# node.net
KiCad netlist of a schematic drawn in EAGLE
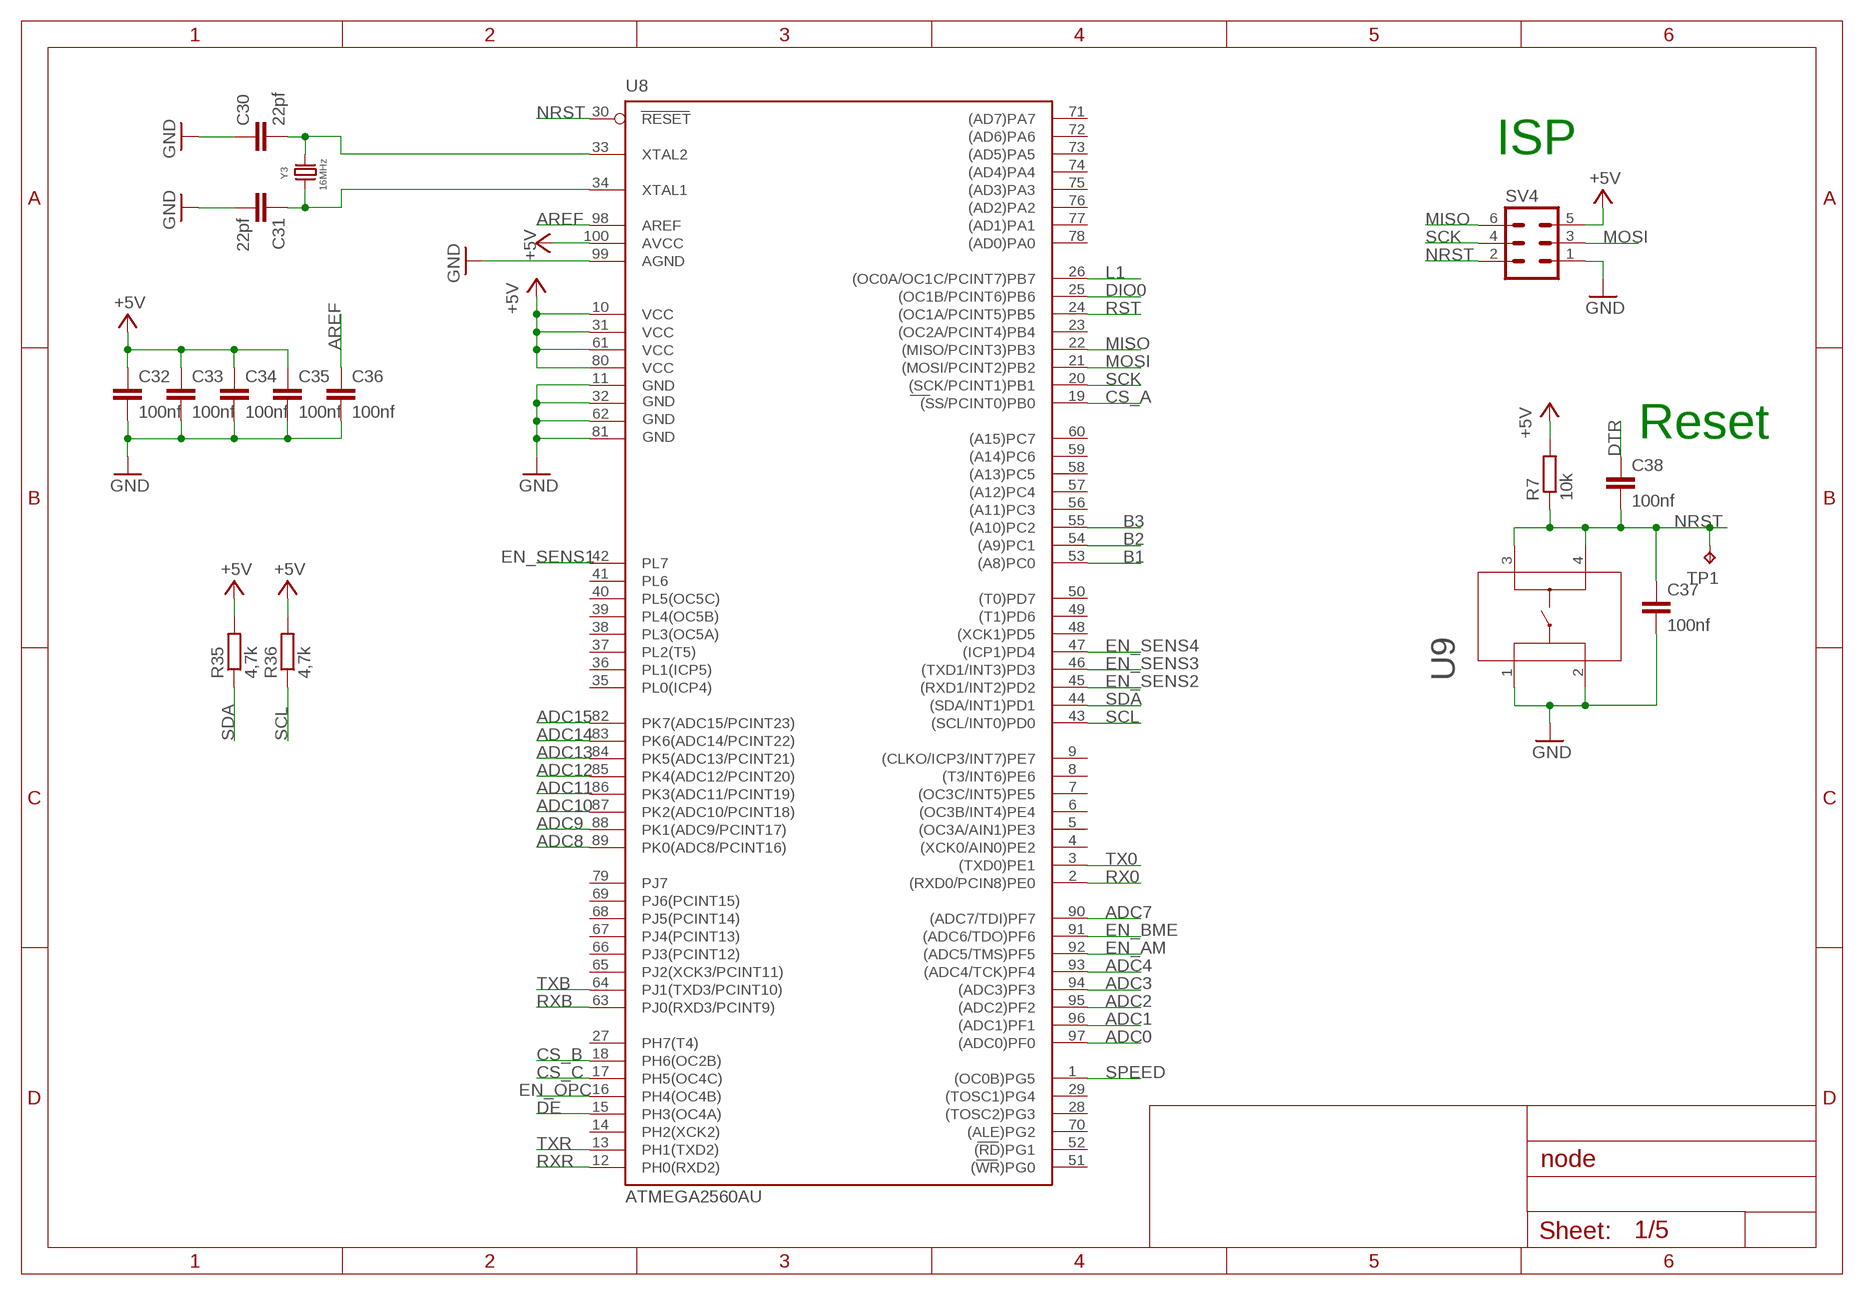
[diagram p0: schematic, sheet 1]
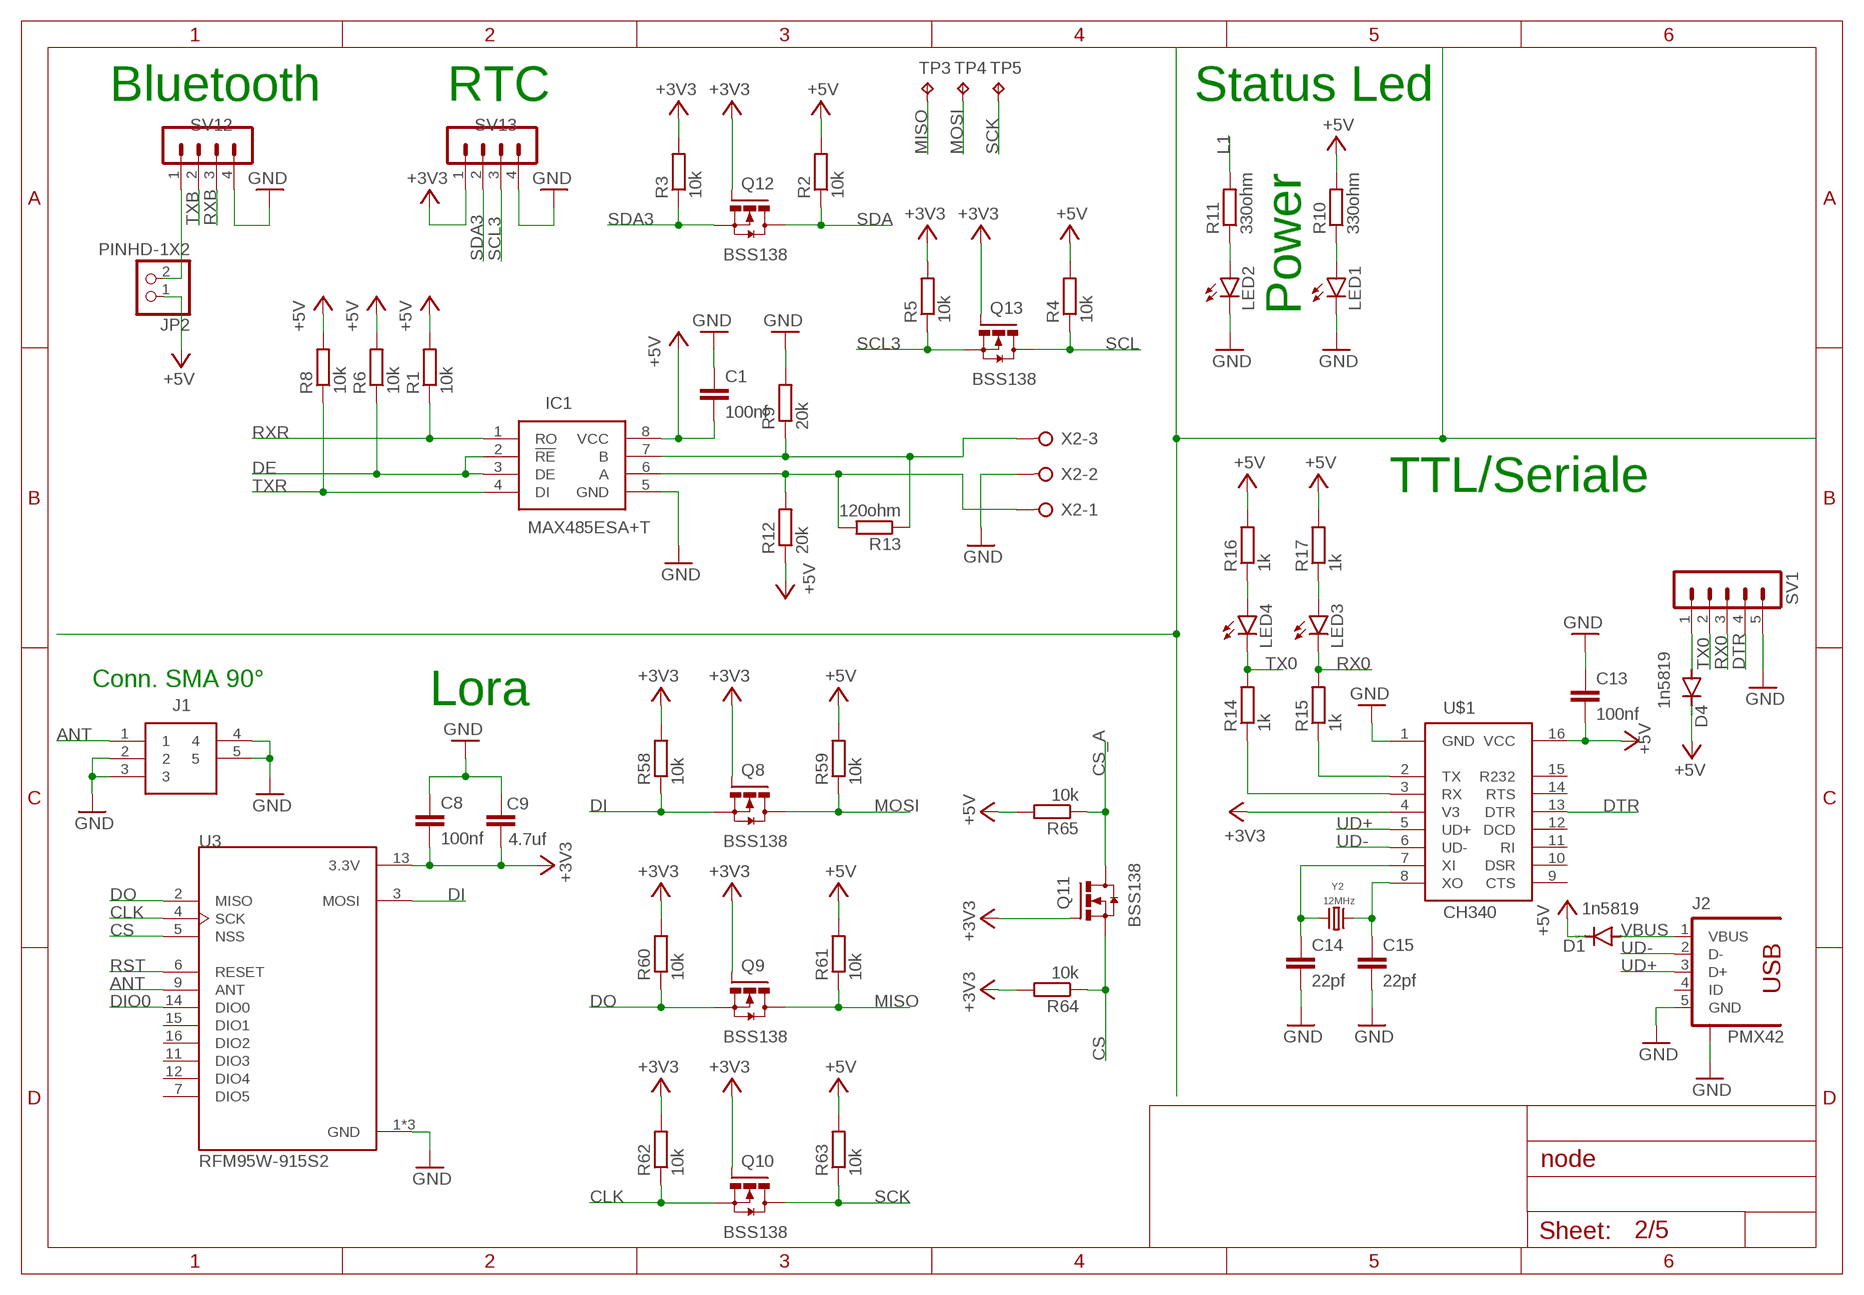
[diagram p1: schematic, sheet 2]
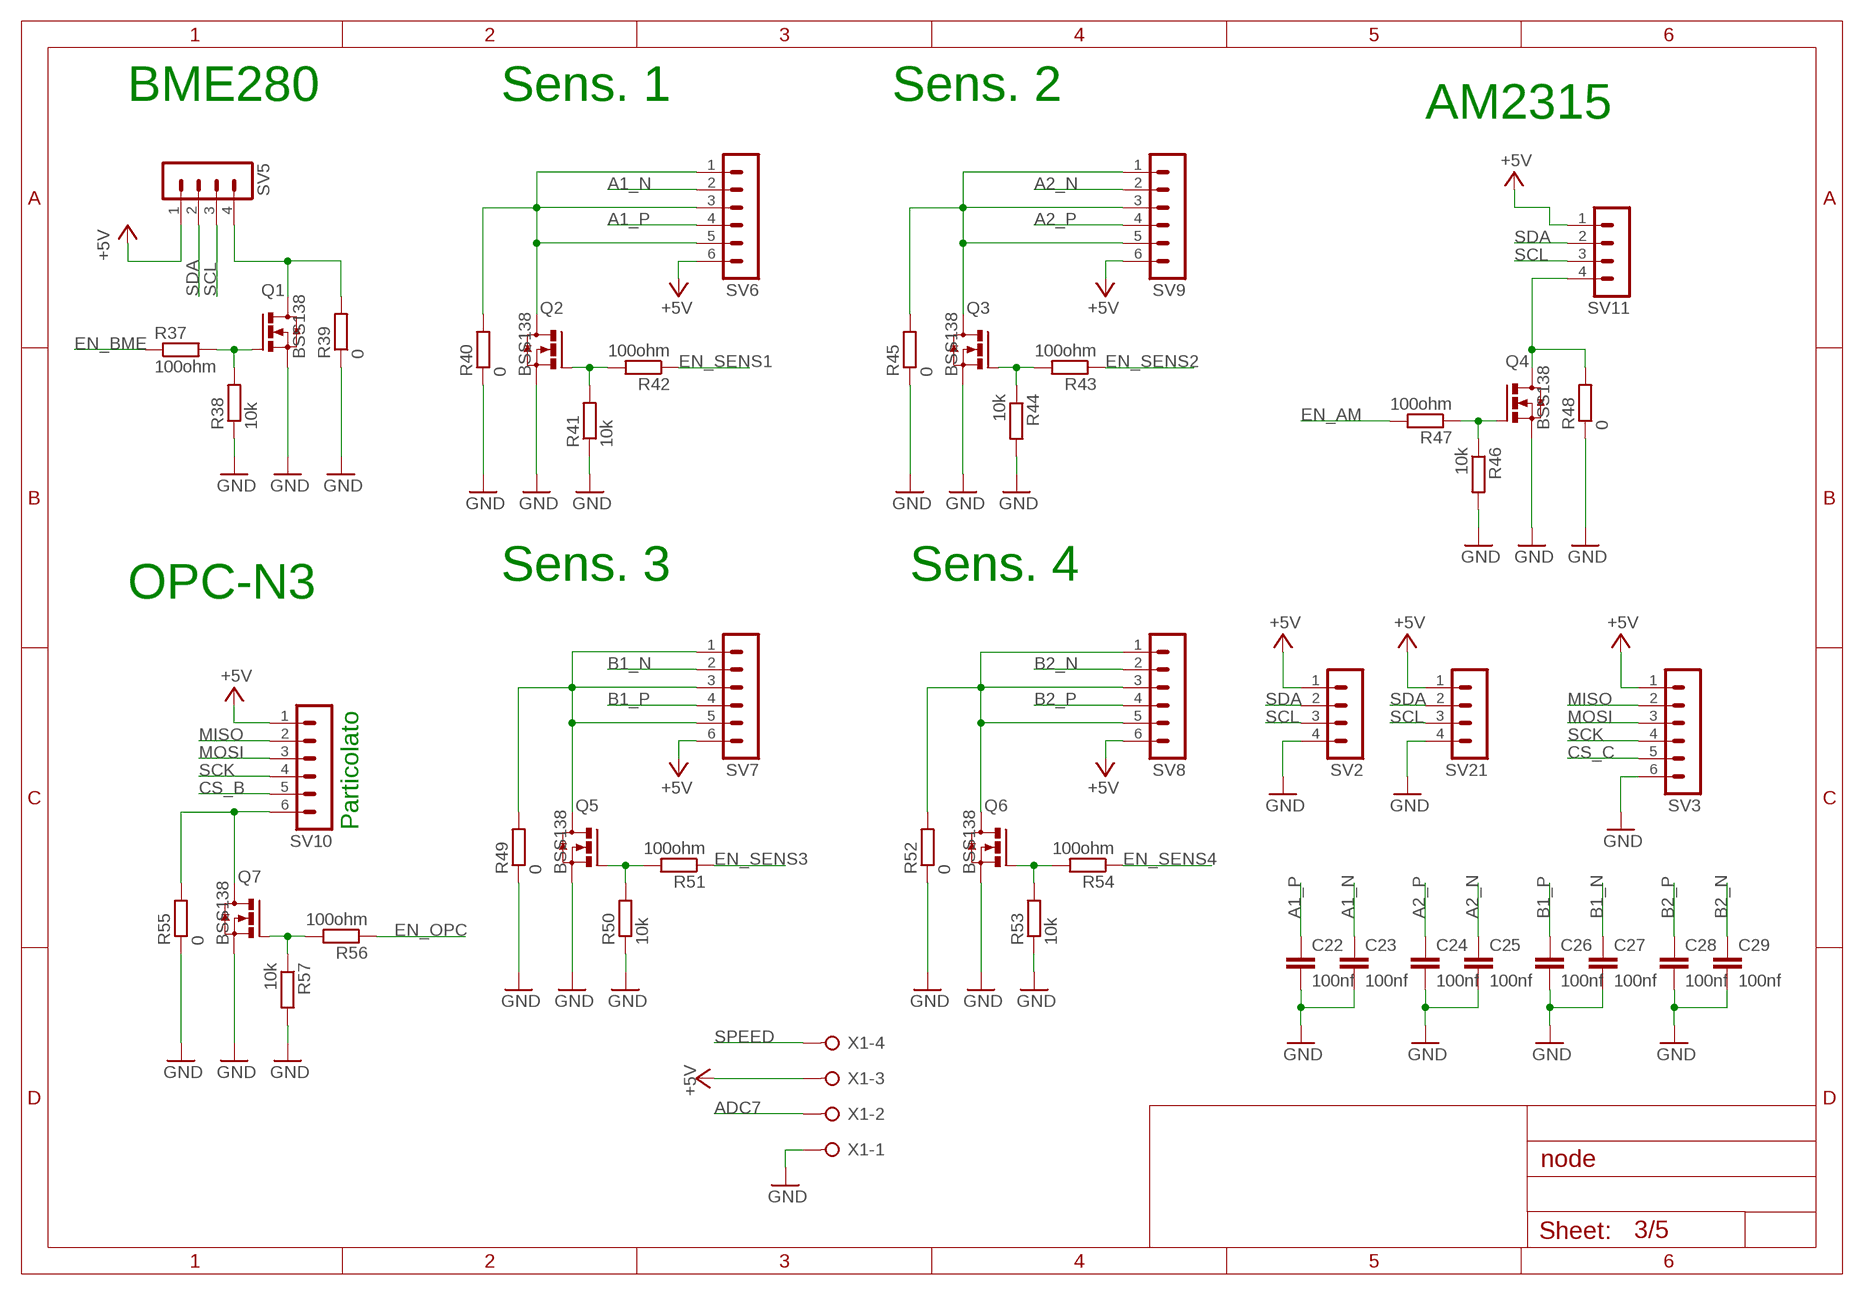
[diagram p2: schematic, sheet 3]
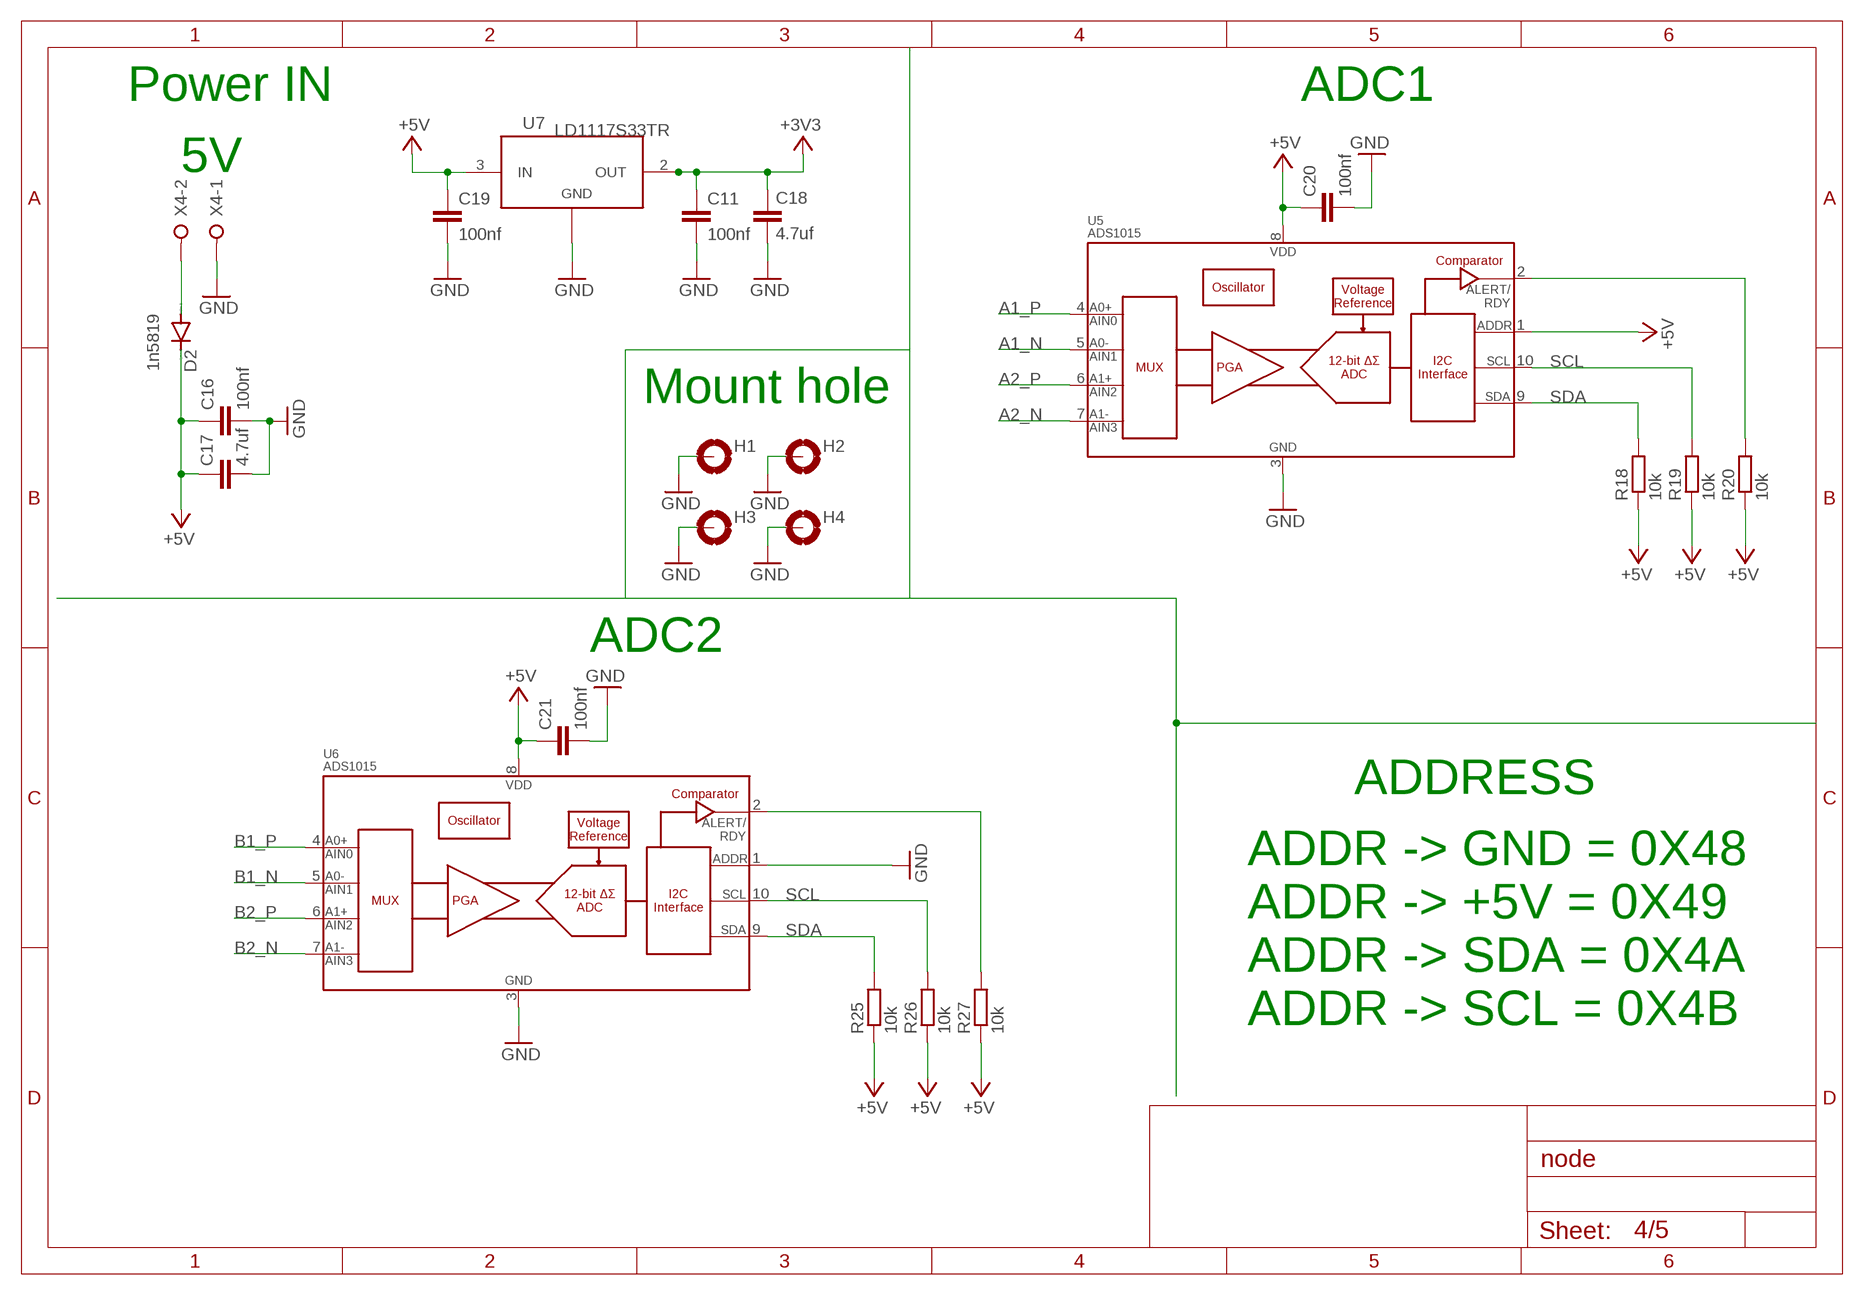
[diagram p3: schematic, sheet 4]
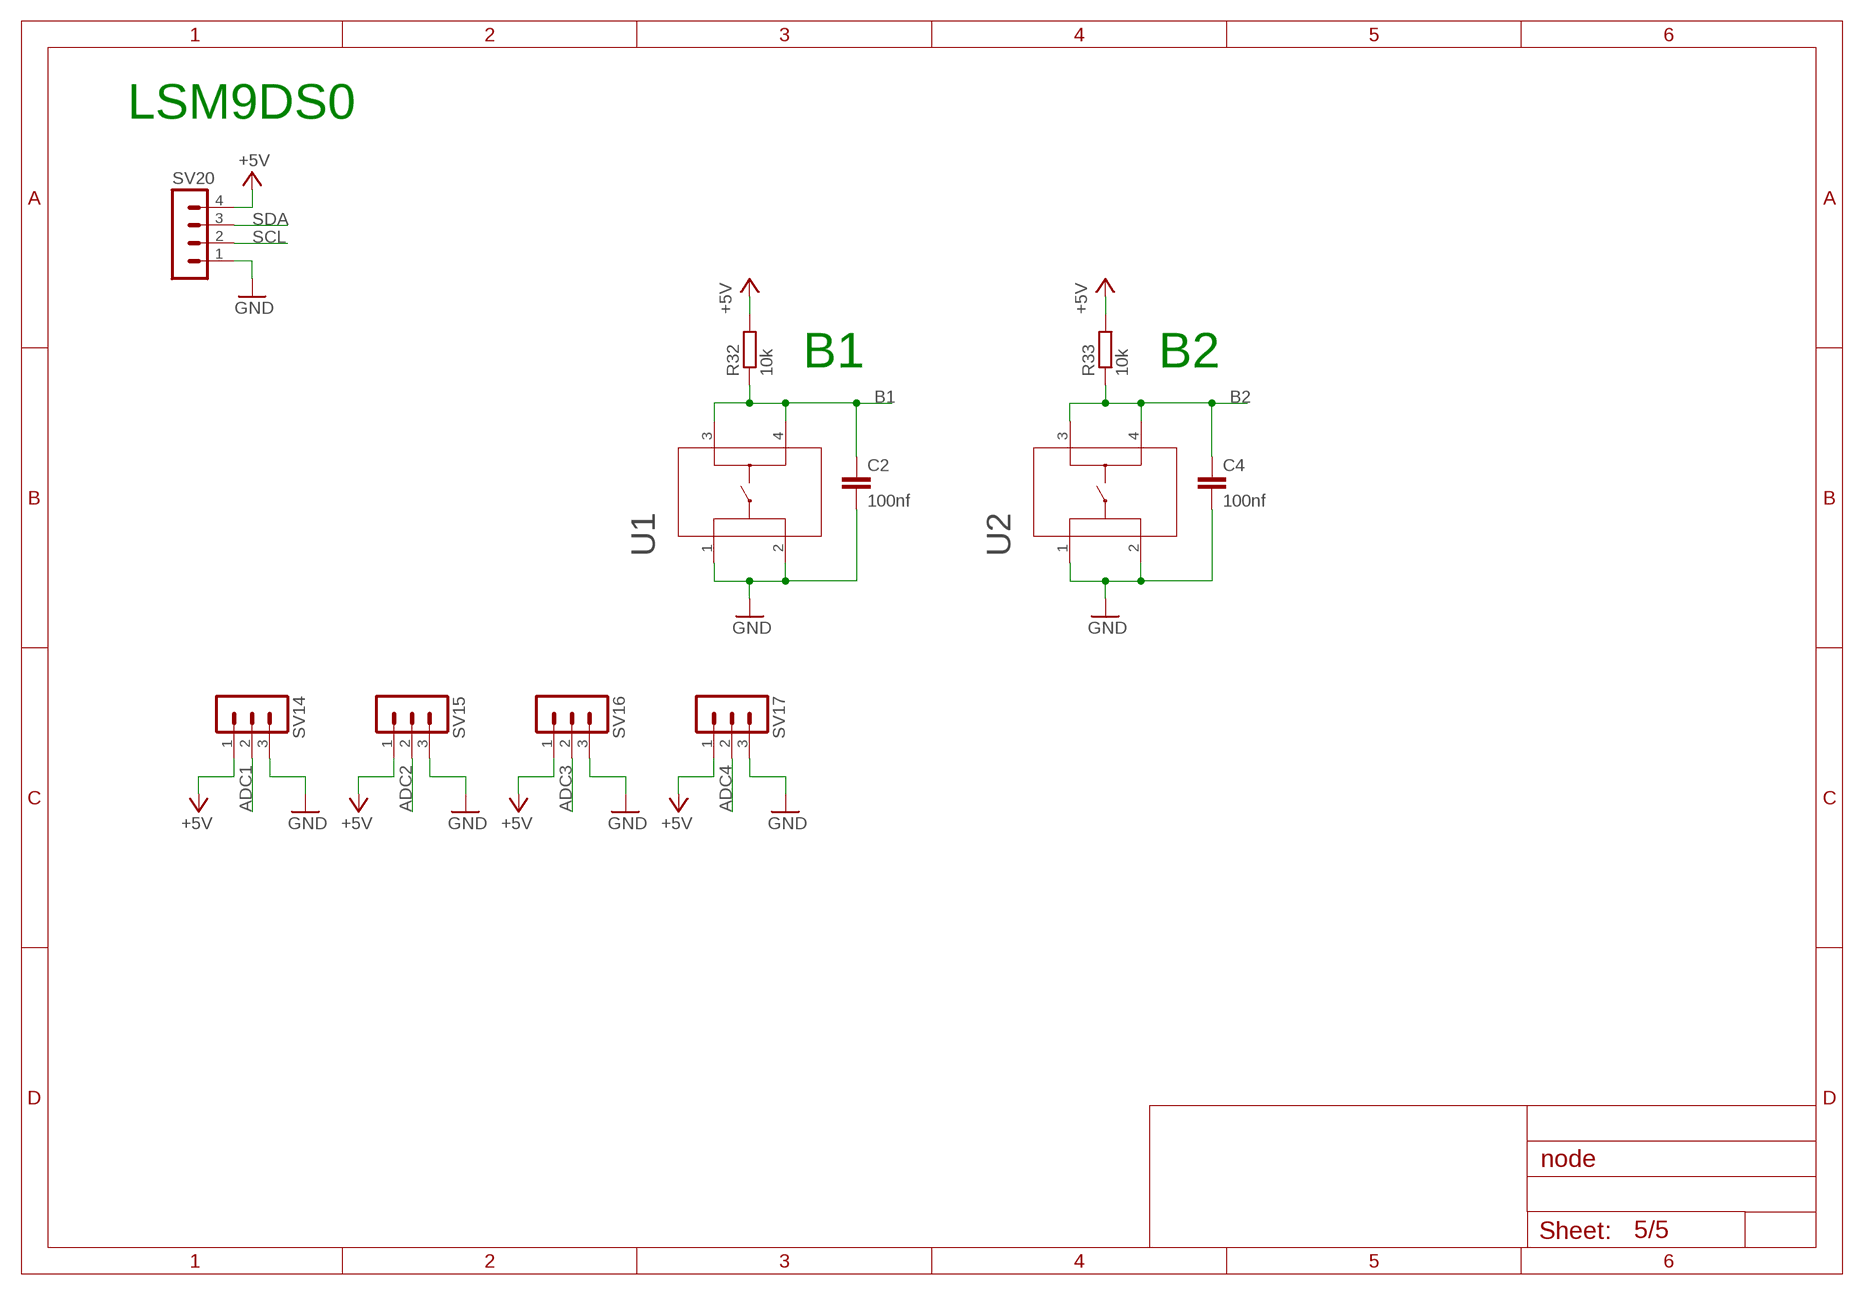
[diagram p4: schematic, sheet 5]

(export (version "E")
  (design (tool "Eeschema 10.0.6"))
  (components
    (comp (ref "C2")
      (value "100nf")
      (footprint "eagle-import:C0805")
      (libsource (lib "eagle-import") (part "C-EUC0805"))
    )
    (comp (ref "C4")
      (value "100nf")
      (footprint "eagle-import:C0805")
      (libsource (lib "eagle-import") (part "C-EUC0805"))
    )
    (comp (ref "R32")
      (value "10k")
      (footprint "eagle-import:R0805")
      (libsource (lib "eagle-import") (part "R-EU_R0805"))
    )
    (comp (ref "R33")
      (value "10k")
      (footprint "eagle-import:R0805")
      (libsource (lib "eagle-import") (part "R-EU_R0805"))
    )
    (comp (ref "SV14")
      (value "MA03-1")
      (footprint "eagle-import:MA03-1")
      (libsource (lib "eagle-import") (part "MA03-1"))
    )
    (comp (ref "SV15")
      (value "MA03-1")
      (footprint "eagle-import:MA03-1")
      (libsource (lib "eagle-import") (part "MA03-1"))
    )
    (comp (ref "SV16")
      (value "MA03-1")
      (footprint "eagle-import:MA03-1")
      (libsource (lib "eagle-import") (part "MA03-1"))
    )
    (comp (ref "SV17")
      (value "MA03-1")
      (footprint "eagle-import:MA03-1")
      (libsource (lib "eagle-import") (part "MA03-1"))
    )
    (comp (ref "SV20")
      (value "MA04-1")
      (footprint "eagle-import:MA04-1")
      (libsource (lib "eagle-import") (part "MA04-1"))
    )
    (comp (ref "U1")
      (value "1-1825910-0")
      (footprint "eagle-import:SWITCH_1-1825910-0")
      (fields (field (name "COPYRIGHT") "Copyright (C) 2016 Accelerated Designs. All rights reserved"))
      (libsource (lib "eagle-import") (part "1-1825910-0"))
    )
    (comp (ref "U2")
      (value "1-1825910-0")
      (footprint "eagle-import:SWITCH_1-1825910-0")
      (fields (field (name "COPYRIGHT") "Copyright (C) 2016 Accelerated Designs. All rights reserved"))
      (libsource (lib "eagle-import") (part "1-1825910-0"))
    )
    (comp (ref "C1")
      (value "100nf")
      (footprint "eagle-import:C0805")
      (libsource (lib "eagle-import") (part "C-EUC0805"))
    )
    (comp (ref "C8")
      (value "100nf")
      (footprint "eagle-import:C0805")
      (libsource (lib "eagle-import") (part "C-EUC0805"))
    )
    (comp (ref "C9")
      (value "4.7uf")
      (footprint "eagle-import:C1206K")
      (libsource (lib "eagle-import") (part "C-EUC1206K"))
    )
    (comp (ref "C13")
      (value "100nf")
      (footprint "eagle-import:C0805")
      (libsource (lib "eagle-import") (part "C-EUC0805"))
    )
    (comp (ref "C14")
      (value "22pf")
      (footprint "eagle-import:C0603")
      (libsource (lib "eagle-import") (part "C-EUC0603"))
    )
    (comp (ref "C15")
      (value "22pf")
      (footprint "eagle-import:C0603")
      (libsource (lib "eagle-import") (part "C-EUC0603"))
    )
    (comp (ref "D1")
      (value "1n5819")
      (footprint "eagle-import:SOD123")
      (libsource (lib "eagle-import") (part "DIODE-SOD123"))
    )
    (comp (ref "D4")
      (value "1n5819")
      (footprint "eagle-import:SOD123")
      (libsource (lib "eagle-import") (part "DIODE-SOD123"))
    )
    (comp (ref "IC1")
      (value "MAX485ESA+T")
      (footprint "eagle-import:SOIC127P600X175-8N")
      (fields (field (name "MOUSER_PART_NUMBER") "700-MAX485ESAT") (field (name "RS_PART_NUMBER") "1900818P"))
      (libsource (lib "eagle-import") (part "MAX485ESA+T"))
    )
    (comp (ref "J1")
      (value "5-1814400-1")
      (footprint "eagle-import:518144001")
      (fields (field (name "MOUSER_PART_NUMBER") "571-5-1814400-1") (field (name "RS_PART_NUMBER") "6163400"))
      (libsource (lib "eagle-import") (part "5-1814400-1"))
    )
    (comp (ref "J2")
      (value "PMX42")
      (footprint "eagle-import:PMX42_56579-0576")
      (libsource (lib "eagle-import") (part "PMX42_56579-0576"))
    )
    (comp (ref "JP2")
      (value "PINHD-1X2")
      (footprint "eagle-import:1X02")
      (libsource (lib "eagle-import") (part "PINHD-1X2"))
    )
    (comp (ref "LED1")
      (value "LEDSML0805")
      (footprint "eagle-import:SML0805")
      (libsource (lib "eagle-import") (part "LEDSML0805"))
    )
    (comp (ref "LED2")
      (value "LEDSML0805")
      (footprint "eagle-import:SML0805")
      (libsource (lib "eagle-import") (part "LEDSML0805"))
    )
    (comp (ref "LED3")
      (value "LEDSML0805")
      (footprint "eagle-import:SML0805")
      (libsource (lib "eagle-import") (part "LEDSML0805"))
    )
    (comp (ref "LED4")
      (value "LEDSML0805")
      (footprint "eagle-import:SML0805")
      (libsource (lib "eagle-import") (part "LEDSML0805"))
    )
    (comp (ref "Q8")
      (value "BSS138")
      (footprint "eagle-import:SOT23-3")
      (fields
        (field (name "DIGIKEY_PART_NUMBER") "BSS138CT-ND")
        (field (name "MANUFACTURER") "ON Semiconductor")
        (field (name "CREATED_BY") "PCBLayout.com")
      )
      (libsource (lib "eagle-import") (part "BSS138"))
    )
    (comp (ref "Q9")
      (value "BSS138")
      (footprint "eagle-import:SOT23-3")
      (fields
        (field (name "DIGIKEY_PART_NUMBER") "BSS138CT-ND")
        (field (name "MANUFACTURER") "ON Semiconductor")
        (field (name "CREATED_BY") "PCBLayout.com")
      )
      (libsource (lib "eagle-import") (part "BSS138"))
    )
    (comp (ref "Q10")
      (value "BSS138")
      (footprint "eagle-import:SOT23-3")
      (fields
        (field (name "DIGIKEY_PART_NUMBER") "BSS138CT-ND")
        (field (name "MANUFACTURER") "ON Semiconductor")
        (field (name "CREATED_BY") "PCBLayout.com")
      )
      (libsource (lib "eagle-import") (part "BSS138"))
    )
    (comp (ref "Q11")
      (value "BSS138")
      (footprint "eagle-import:SOT23-3")
      (fields
        (field (name "DIGIKEY_PART_NUMBER") "BSS138CT-ND")
        (field (name "MANUFACTURER") "ON Semiconductor")
        (field (name "CREATED_BY") "PCBLayout.com")
      )
      (libsource (lib "eagle-import") (part "BSS138"))
    )
    (comp (ref "Q12")
      (value "BSS138")
      (footprint "eagle-import:SOT23-3")
      (fields
        (field (name "DIGIKEY_PART_NUMBER") "BSS138CT-ND")
        (field (name "MANUFACTURER") "ON Semiconductor")
        (field (name "CREATED_BY") "PCBLayout.com")
      )
      (libsource (lib "eagle-import") (part "BSS138"))
    )
    (comp (ref "Q13")
      (value "BSS138")
      (footprint "eagle-import:SOT23-3")
      (fields
        (field (name "DIGIKEY_PART_NUMBER") "BSS138CT-ND")
        (field (name "MANUFACTURER") "ON Semiconductor")
        (field (name "CREATED_BY") "PCBLayout.com")
      )
      (libsource (lib "eagle-import") (part "BSS138"))
    )
    (comp (ref "R1")
      (value "10k")
      (footprint "eagle-import:R0805")
      (libsource (lib "eagle-import") (part "R-EU_R0805"))
    )
    (comp (ref "R2")
      (value "10k")
      (footprint "eagle-import:R0805")
      (libsource (lib "eagle-import") (part "R-EU_R0805"))
    )
    (comp (ref "R3")
      (value "10k")
      (footprint "eagle-import:R0805")
      (libsource (lib "eagle-import") (part "R-EU_R0805"))
    )
    (comp (ref "R4")
      (value "10k")
      (footprint "eagle-import:R0805")
      (libsource (lib "eagle-import") (part "R-EU_R0805"))
    )
    (comp (ref "R5")
      (value "10k")
      (footprint "eagle-import:R0805")
      (libsource (lib "eagle-import") (part "R-EU_R0805"))
    )
    (comp (ref "R6")
      (value "10k")
      (footprint "eagle-import:R0805")
      (libsource (lib "eagle-import") (part "R-EU_R0805"))
    )
    (comp (ref "R8")
      (value "10k")
      (footprint "eagle-import:R0805")
      (libsource (lib "eagle-import") (part "R-EU_R0805"))
    )
    (comp (ref "R9")
      (value "20k")
      (footprint "eagle-import:R0805")
      (libsource (lib "eagle-import") (part "R-EU_R0805"))
    )
    (comp (ref "R10")
      (value "330ohm")
      (footprint "eagle-import:R0805")
      (libsource (lib "eagle-import") (part "R-EU_R0805"))
    )
    (comp (ref "R11")
      (value "330ohm")
      (footprint "eagle-import:R0805")
      (libsource (lib "eagle-import") (part "R-EU_R0805"))
    )
    (comp (ref "R12")
      (value "20k")
      (footprint "eagle-import:R0805")
      (libsource (lib "eagle-import") (part "R-EU_R0805"))
    )
    (comp (ref "R13")
      (value "120ohm")
      (footprint "eagle-import:R0805")
      (libsource (lib "eagle-import") (part "R-EU_R0805"))
    )
    (comp (ref "R14")
      (value "1k")
      (footprint "eagle-import:R0805")
      (libsource (lib "eagle-import") (part "R-EU_R0805"))
    )
    (comp (ref "R15")
      (value "1k")
      (footprint "eagle-import:R0805")
      (libsource (lib "eagle-import") (part "R-EU_R0805"))
    )
    (comp (ref "R16")
      (value "1k")
      (footprint "eagle-import:R0805")
      (libsource (lib "eagle-import") (part "R-EU_R0805"))
    )
    (comp (ref "R17")
      (value "1k")
      (footprint "eagle-import:R0805")
      (libsource (lib "eagle-import") (part "R-EU_R0805"))
    )
    (comp (ref "R58")
      (value "10k")
      (footprint "eagle-import:R0805")
      (libsource (lib "eagle-import") (part "R-EU_R0805"))
    )
    (comp (ref "R59")
      (value "10k")
      (footprint "eagle-import:R0805")
      (libsource (lib "eagle-import") (part "R-EU_R0805"))
    )
    (comp (ref "R60")
      (value "10k")
      (footprint "eagle-import:R0805")
      (libsource (lib "eagle-import") (part "R-EU_R0805"))
    )
    (comp (ref "R61")
      (value "10k")
      (footprint "eagle-import:R0805")
      (libsource (lib "eagle-import") (part "R-EU_R0805"))
    )
    (comp (ref "R62")
      (value "10k")
      (footprint "eagle-import:R0805")
      (libsource (lib "eagle-import") (part "R-EU_R0805"))
    )
    (comp (ref "R63")
      (value "10k")
      (footprint "eagle-import:R0805")
      (libsource (lib "eagle-import") (part "R-EU_R0805"))
    )
    (comp (ref "R64")
      (value "10k")
      (footprint "eagle-import:R0805")
      (libsource (lib "eagle-import") (part "R-EU_R0805"))
    )
    (comp (ref "R65")
      (value "10k")
      (footprint "eagle-import:R0805")
      (libsource (lib "eagle-import") (part "R-EU_R0805"))
    )
    (comp (ref "SV1")
      (value "MA05-1")
      (footprint "eagle-import:MA05-1")
      (libsource (lib "eagle-import") (part "MA05-1"))
    )
    (comp (ref "SV12")
      (value "MA04-1")
      (footprint "eagle-import:MA04-1")
      (libsource (lib "eagle-import") (part "MA04-1"))
    )
    (comp (ref "SV13")
      (value "MA04-1")
      (footprint "eagle-import:MA04-1")
      (libsource (lib "eagle-import") (part "MA04-1"))
    )
    (comp (ref "TP3")
      (value "TPTP13R")
      (footprint "eagle-import:TP13R")
      (libsource (lib "eagle-import") (part "TPTP13R"))
    )
    (comp (ref "TP4")
      (value "TPTP13R")
      (footprint "eagle-import:TP13R")
      (libsource (lib "eagle-import") (part "TPTP13R"))
    )
    (comp (ref "TP5")
      (value "TPTP13R")
      (footprint "eagle-import:TP13R")
      (libsource (lib "eagle-import") (part "TPTP13R"))
    )
    (comp (ref "U$1")
      (value "CH340")
      (footprint "eagle-import:SOIC16")
      (fields (field (name "MF") "Eaton"))
      (libsource (lib "eagle-import") (part "CH340"))
    )
    (comp (ref "U3")
      (value "RFM95W-915S2")
      (footprint "eagle-import:XCVR_RFM95W-915S2")
      (fields (field (name "MF") "RF Solutions"))
      (libsource (lib "eagle-import") (part "RFM95W-915S2"))
    )
    (comp (ref "X2")
      (value "W237-3E")
      (footprint "eagle-import:W237-3E")
      (libsource (lib "eagle-import") (part "W237-3E"))
    )
    (comp (ref "Y2")
      (value "12MHz")
      (footprint "eagle-import:WE-XTAL_HC49_4H")
      (fields (field (name "TOLERANCE") "±30ppm"))
      (libsource (lib "eagle-import") (part "WE-XTAL_HC49/4H_830003063B"))
    )
    (comp (ref "C11")
      (value "100nf")
      (footprint "eagle-import:C0805")
      (libsource (lib "eagle-import") (part "C-EUC0805"))
    )
    (comp (ref "C16")
      (value "100nf")
      (footprint "eagle-import:C0805")
      (libsource (lib "eagle-import") (part "C-EUC0805"))
    )
    (comp (ref "C17")
      (value "4.7uf")
      (footprint "eagle-import:C1206K")
      (libsource (lib "eagle-import") (part "C-EUC1206K"))
    )
    (comp (ref "C18")
      (value "4.7uf")
      (footprint "eagle-import:C1206K")
      (libsource (lib "eagle-import") (part "C-EUC1206K"))
    )
    (comp (ref "C19")
      (value "100nf")
      (footprint "eagle-import:C0805")
      (libsource (lib "eagle-import") (part "C-EUC0805"))
    )
    (comp (ref "C20")
      (value "100nf")
      (footprint "eagle-import:C0805")
      (libsource (lib "eagle-import") (part "C-EUC0805"))
    )
    (comp (ref "C21")
      (value "100nf")
      (footprint "eagle-import:C0805")
      (libsource (lib "eagle-import") (part "C-EUC0805"))
    )
    (comp (ref "D2")
      (value "1n5819")
      (footprint "eagle-import:SOD123")
      (libsource (lib "eagle-import") (part "DIODE-SOD123"))
    )
    (comp (ref "H1")
      (value "MOUNT-PAD-ROUND3.2")
      (footprint "eagle-import:3,2-PAD")
      (libsource (lib "eagle-import") (part "MOUNT-PAD-ROUND3.2"))
    )
    (comp (ref "H2")
      (value "MOUNT-PAD-ROUND3.2")
      (footprint "eagle-import:3,2-PAD")
      (libsource (lib "eagle-import") (part "MOUNT-PAD-ROUND3.2"))
    )
    (comp (ref "H3")
      (value "MOUNT-PAD-ROUND3.2")
      (footprint "eagle-import:3,2-PAD")
      (libsource (lib "eagle-import") (part "MOUNT-PAD-ROUND3.2"))
    )
    (comp (ref "H4")
      (value "MOUNT-PAD-ROUND3.2")
      (footprint "eagle-import:3,2-PAD")
      (libsource (lib "eagle-import") (part "MOUNT-PAD-ROUND3.2"))
    )
    (comp (ref "R18")
      (value "10k")
      (footprint "eagle-import:R0805")
      (libsource (lib "eagle-import") (part "R-EU_R0805"))
    )
    (comp (ref "R19")
      (value "10k")
      (footprint "eagle-import:R0805")
      (libsource (lib "eagle-import") (part "R-EU_R0805"))
    )
    (comp (ref "R20")
      (value "10k")
      (footprint "eagle-import:R0805")
      (libsource (lib "eagle-import") (part "R-EU_R0805"))
    )
    (comp (ref "R25")
      (value "10k")
      (footprint "eagle-import:R0805")
      (libsource (lib "eagle-import") (part "R-EU_R0805"))
    )
    (comp (ref "R26")
      (value "10k")
      (footprint "eagle-import:R0805")
      (libsource (lib "eagle-import") (part "R-EU_R0805"))
    )
    (comp (ref "R27")
      (value "10k")
      (footprint "eagle-import:R0805")
      (libsource (lib "eagle-import") (part "R-EU_R0805"))
    )
    (comp (ref "U5")
      (value "ADS1015")
      (footprint "eagle-import:MSOP10")
      (libsource (lib "eagle-import") (part "ADS1015"))
    )
    (comp (ref "U6")
      (value "ADS1015")
      (footprint "eagle-import:MSOP10")
      (libsource (lib "eagle-import") (part "ADS1015"))
    )
    (comp (ref "U7")
      (value "LD1117S33TR")
      (footprint "eagle-import:SOT-223")
      (fields
        (field (name "DIGIKEY_PART_NUMBER") "497-1242-2-ND")
        (field (name "MANUFACTURER") "STMicroelectronics")
        (field (name "CREATED_BY") "PCBLayout.com")
      )
      (libsource (lib "eagle-import") (part "LD1117S33TR"))
    )
    (comp (ref "X4")
      (value "W237-02P")
      (footprint "eagle-import:W237-132")
      (libsource (lib "eagle-import") (part "W237-02P"))
    )
    (comp (ref "C30")
      (value "22pf")
      (footprint "eagle-import:C0603")
      (libsource (lib "eagle-import") (part "C-EUC0603"))
    )
    (comp (ref "C31")
      (value "22pf")
      (footprint "eagle-import:C0603")
      (libsource (lib "eagle-import") (part "C-EUC0603"))
    )
    (comp (ref "C32")
      (value "100nf")
      (footprint "eagle-import:C0805")
      (libsource (lib "eagle-import") (part "C-EUC0805"))
    )
    (comp (ref "C33")
      (value "100nf")
      (footprint "eagle-import:C0805")
      (libsource (lib "eagle-import") (part "C-EUC0805"))
    )
    (comp (ref "C34")
      (value "100nf")
      (footprint "eagle-import:C0805")
      (libsource (lib "eagle-import") (part "C-EUC0805"))
    )
    (comp (ref "C35")
      (value "100nf")
      (footprint "eagle-import:C0805")
      (libsource (lib "eagle-import") (part "C-EUC0805"))
    )
    (comp (ref "C36")
      (value "100nf")
      (footprint "eagle-import:C0805")
      (libsource (lib "eagle-import") (part "C-EUC0805"))
    )
    (comp (ref "C37")
      (value "100nf")
      (footprint "eagle-import:C0805")
      (libsource (lib "eagle-import") (part "C-EUC0805"))
    )
    (comp (ref "C38")
      (value "100nf")
      (footprint "eagle-import:C0805")
      (libsource (lib "eagle-import") (part "C-EUC0805"))
    )
    (comp (ref "R7")
      (value "10k")
      (footprint "eagle-import:R0805")
      (libsource (lib "eagle-import") (part "R-EU_R0805"))
    )
    (comp (ref "R35")
      (value "4,7k")
      (footprint "eagle-import:R0603")
      (libsource (lib "eagle-import") (part "R-EU_R0603"))
    )
    (comp (ref "R36")
      (value "4,7k")
      (footprint "eagle-import:R0603")
      (libsource (lib "eagle-import") (part "R-EU_R0603"))
    )
    (comp (ref "SV4")
      (value "MA03-2")
      (footprint "eagle-import:MA03-2")
      (libsource (lib "eagle-import") (part "MA03-2"))
    )
    (comp (ref "TP1")
      (value "TPTP13R")
      (footprint "eagle-import:TP13R")
      (libsource (lib "eagle-import") (part "TPTP13R"))
    )
    (comp (ref "U8")
      (value "ATMEGA2560AU")
      (footprint "eagle-import:TQFP100")
      (libsource (lib "eagle-import") (part "ATMEGA2560AU"))
    )
    (comp (ref "U9")
      (value "1-1825910-0")
      (footprint "eagle-import:SWITCH_1-1825910-0")
      (fields (field (name "COPYRIGHT") "Copyright (C) 2016 Accelerated Designs. All rights reserved"))
      (libsource (lib "eagle-import") (part "1-1825910-0"))
    )
    (comp (ref "Y3")
      (value "16MHz")
      (footprint "eagle-import:WE-XTAL_HC49_4H")
      (fields (field (name "TOLERANCE") "±30ppm"))
      (libsource (lib "eagle-import") (part "WE-XTAL_HC49/4H_830003240B"))
    )
    (comp (ref "C22")
      (value "100nf")
      (footprint "eagle-import:C0805")
      (libsource (lib "eagle-import") (part "C-EUC0805"))
    )
    (comp (ref "C23")
      (value "100nf")
      (footprint "eagle-import:C0805")
      (libsource (lib "eagle-import") (part "C-EUC0805"))
    )
    (comp (ref "C24")
      (value "100nf")
      (footprint "eagle-import:C0805")
      (libsource (lib "eagle-import") (part "C-EUC0805"))
    )
    (comp (ref "C25")
      (value "100nf")
      (footprint "eagle-import:C0805")
      (libsource (lib "eagle-import") (part "C-EUC0805"))
    )
    (comp (ref "C26")
      (value "100nf")
      (footprint "eagle-import:C0805")
      (libsource (lib "eagle-import") (part "C-EUC0805"))
    )
    (comp (ref "C27")
      (value "100nf")
      (footprint "eagle-import:C0805")
      (libsource (lib "eagle-import") (part "C-EUC0805"))
    )
    (comp (ref "C28")
      (value "100nf")
      (footprint "eagle-import:C0805")
      (libsource (lib "eagle-import") (part "C-EUC0805"))
    )
    (comp (ref "C29")
      (value "100nf")
      (footprint "eagle-import:C0805")
      (libsource (lib "eagle-import") (part "C-EUC0805"))
    )
    (comp (ref "Q1")
      (value "BSS138")
      (footprint "eagle-import:SOT23-3")
      (fields
        (field (name "DIGIKEY_PART_NUMBER") "BSS138CT-ND")
        (field (name "MANUFACTURER") "ON Semiconductor")
        (field (name "CREATED_BY") "PCBLayout.com")
      )
      (libsource (lib "eagle-import") (part "BSS138"))
    )
    (comp (ref "Q2")
      (value "BSS138")
      (footprint "eagle-import:SOT23-3")
      (fields
        (field (name "DIGIKEY_PART_NUMBER") "BSS138CT-ND")
        (field (name "MANUFACTURER") "ON Semiconductor")
        (field (name "CREATED_BY") "PCBLayout.com")
      )
      (libsource (lib "eagle-import") (part "BSS138"))
    )
    (comp (ref "Q3")
      (value "BSS138")
      (footprint "eagle-import:SOT23-3")
      (fields
        (field (name "DIGIKEY_PART_NUMBER") "BSS138CT-ND")
        (field (name "MANUFACTURER") "ON Semiconductor")
        (field (name "CREATED_BY") "PCBLayout.com")
      )
      (libsource (lib "eagle-import") (part "BSS138"))
    )
    (comp (ref "Q4")
      (value "BSS138")
      (footprint "eagle-import:SOT23-3")
      (fields
        (field (name "DIGIKEY_PART_NUMBER") "BSS138CT-ND")
        (field (name "MANUFACTURER") "ON Semiconductor")
        (field (name "CREATED_BY") "PCBLayout.com")
      )
      (libsource (lib "eagle-import") (part "BSS138"))
    )
    (comp (ref "Q5")
      (value "BSS138")
      (footprint "eagle-import:SOT23-3")
      (fields
        (field (name "DIGIKEY_PART_NUMBER") "BSS138CT-ND")
        (field (name "MANUFACTURER") "ON Semiconductor")
        (field (name "CREATED_BY") "PCBLayout.com")
      )
      (libsource (lib "eagle-import") (part "BSS138"))
    )
    (comp (ref "Q6")
      (value "BSS138")
      (footprint "eagle-import:SOT23-3")
      (fields
        (field (name "DIGIKEY_PART_NUMBER") "BSS138CT-ND")
        (field (name "MANUFACTURER") "ON Semiconductor")
        (field (name "CREATED_BY") "PCBLayout.com")
      )
      (libsource (lib "eagle-import") (part "BSS138"))
    )
    (comp (ref "Q7")
      (value "BSS138")
      (footprint "eagle-import:SOT23-3")
      (fields
        (field (name "DIGIKEY_PART_NUMBER") "BSS138CT-ND")
        (field (name "MANUFACTURER") "ON Semiconductor")
        (field (name "CREATED_BY") "PCBLayout.com")
      )
      (libsource (lib "eagle-import") (part "BSS138"))
    )
    (comp (ref "R37")
      (value "100ohm")
      (footprint "eagle-import:R0805W")
      (libsource (lib "eagle-import") (part "R-EU_R0805W"))
    )
    (comp (ref "R38")
      (value "10k")
      (footprint "eagle-import:R0805W")
      (libsource (lib "eagle-import") (part "R-EU_R0805W"))
    )
    (comp (ref "R39")
      (value "0")
      (footprint "eagle-import:R0603")
      (libsource (lib "eagle-import") (part "R-EU_R0603"))
    )
    (comp (ref "R40")
      (value "0")
      (footprint "eagle-import:R0603")
      (libsource (lib "eagle-import") (part "R-EU_R0603"))
    )
    (comp (ref "R41")
      (value "10k")
      (footprint "eagle-import:R0805W")
      (libsource (lib "eagle-import") (part "R-EU_R0805W"))
    )
    (comp (ref "R42")
      (value "100ohm")
      (footprint "eagle-import:R0805W")
      (libsource (lib "eagle-import") (part "R-EU_R0805W"))
    )
    (comp (ref "R43")
      (value "100ohm")
      (footprint "eagle-import:R0805W")
      (libsource (lib "eagle-import") (part "R-EU_R0805W"))
    )
    (comp (ref "R44")
      (value "10k")
      (footprint "eagle-import:R0805W")
      (libsource (lib "eagle-import") (part "R-EU_R0805W"))
    )
    (comp (ref "R45")
      (value "0")
      (footprint "eagle-import:R0603")
      (libsource (lib "eagle-import") (part "R-EU_R0603"))
    )
    (comp (ref "R46")
      (value "10k")
      (footprint "eagle-import:R0805W")
      (libsource (lib "eagle-import") (part "R-EU_R0805W"))
    )
    (comp (ref "R47")
      (value "100ohm")
      (footprint "eagle-import:R0805W")
      (libsource (lib "eagle-import") (part "R-EU_R0805W"))
    )
    (comp (ref "R48")
      (value "0")
      (footprint "eagle-import:R0603")
      (libsource (lib "eagle-import") (part "R-EU_R0603"))
    )
    (comp (ref "R49")
      (value "0")
      (footprint "eagle-import:R0603")
      (libsource (lib "eagle-import") (part "R-EU_R0603"))
    )
    (comp (ref "R50")
      (value "10k")
      (footprint "eagle-import:R0805W")
      (libsource (lib "eagle-import") (part "R-EU_R0805W"))
    )
    (comp (ref "R51")
      (value "100ohm")
      (footprint "eagle-import:R0805W")
      (libsource (lib "eagle-import") (part "R-EU_R0805W"))
    )
    (comp (ref "R52")
      (value "0")
      (footprint "eagle-import:R0603")
      (libsource (lib "eagle-import") (part "R-EU_R0603"))
    )
    (comp (ref "R53")
      (value "10k")
      (footprint "eagle-import:R0805W")
      (libsource (lib "eagle-import") (part "R-EU_R0805W"))
    )
    (comp (ref "R54")
      (value "100ohm")
      (footprint "eagle-import:R0805W")
      (libsource (lib "eagle-import") (part "R-EU_R0805W"))
    )
    (comp (ref "R55")
      (value "0")
      (footprint "eagle-import:R0603")
      (libsource (lib "eagle-import") (part "R-EU_R0603"))
    )
    (comp (ref "R56")
      (value "100ohm")
      (footprint "eagle-import:R0805W")
      (libsource (lib "eagle-import") (part "R-EU_R0805W"))
    )
    (comp (ref "R57")
      (value "10k")
      (footprint "eagle-import:R0805W")
      (libsource (lib "eagle-import") (part "R-EU_R0805W"))
    )
    (comp (ref "SV2")
      (value "MA04-1")
      (footprint "eagle-import:MA04-1")
      (libsource (lib "eagle-import") (part "MA04-1"))
    )
    (comp (ref "SV3")
      (value "MA06-1")
      (footprint "eagle-import:MA06-1")
      (libsource (lib "eagle-import") (part "MA06-1"))
    )
    (comp (ref "SV5")
      (value "MA04-1")
      (footprint "eagle-import:MA04-1")
      (libsource (lib "eagle-import") (part "MA04-1"))
    )
    (comp (ref "SV6")
      (value "MA06-1")
      (footprint "eagle-import:MA06-1")
      (libsource (lib "eagle-import") (part "MA06-1"))
    )
    (comp (ref "SV7")
      (value "MA06-1")
      (footprint "eagle-import:MA06-1")
      (libsource (lib "eagle-import") (part "MA06-1"))
    )
    (comp (ref "SV8")
      (value "MA06-1")
      (footprint "eagle-import:MA06-1")
      (libsource (lib "eagle-import") (part "MA06-1"))
    )
    (comp (ref "SV9")
      (value "MA06-1")
      (footprint "eagle-import:MA06-1")
      (libsource (lib "eagle-import") (part "MA06-1"))
    )
    (comp (ref "SV10")
      (value "MA06-1")
      (footprint "eagle-import:MA06-1")
      (libsource (lib "eagle-import") (part "MA06-1"))
    )
    (comp (ref "SV11")
      (value "MA04-1")
      (footprint "eagle-import:MA04-1")
      (libsource (lib "eagle-import") (part "MA04-1"))
    )
    (comp (ref "SV21")
      (value "MA04-1")
      (footprint "eagle-import:MA04-1")
      (libsource (lib "eagle-import") (part "MA04-1"))
    )
    (comp (ref "X1")
      (value "W237-04P")
      (footprint "eagle-import:W237-4P")
      (libsource (lib "eagle-import") (part "W237-04P"))
    )
  )
  (nets
    (net (code "1") (name "+3V3") (class "Default")
      (node (ref "C11") (pin "1") (pinfunction "1_1") (pintype "passive"))
      (node (ref "C18") (pin "1") (pinfunction "1_1") (pintype "passive"))
      (node (ref "C8") (pin "2") (pinfunction "2_2") (pintype "passive"))
      (node (ref "C9") (pin "1") (pinfunction "1_1") (pintype "passive"))
      (node (ref "Q10") (pin "1") (pinfunction "G_1") (pintype "passive"))
      (node (ref "Q11") (pin "1") (pinfunction "G_1") (pintype "passive"))
      (node (ref "Q12") (pin "1") (pinfunction "G_1") (pintype "passive"))
      (node (ref "Q13") (pin "1") (pinfunction "G_1") (pintype "passive"))
      (node (ref "Q8") (pin "1") (pinfunction "G_1") (pintype "passive"))
      (node (ref "Q9") (pin "1") (pinfunction "G_1") (pintype "passive"))
      (node (ref "R3") (pin "2") (pinfunction "2_2") (pintype "passive"))
      (node (ref "R5") (pin "2") (pinfunction "2_2") (pintype "passive"))
      (node (ref "R58") (pin "2") (pinfunction "2_2") (pintype "passive"))
      (node (ref "R60") (pin "2") (pinfunction "2_2") (pintype "passive"))
      (node (ref "R62") (pin "2") (pinfunction "2_2") (pintype "passive"))
      (node (ref "R64") (pin "2") (pinfunction "2_2") (pintype "passive"))
      (node (ref "SV13") (pin "1") (pinfunction "1_1") (pintype "passive"))
      (node (ref "U$1") (pin "4") (pinfunction "V3_4") (pintype "power_in"))
      (node (ref "U3") (pin "13") (pinfunction "3.3V_13") (pintype "power_in"))
      (node (ref "U7") (pin "2") (pinfunction "OUT_2") (pintype "output"))
      (node (ref "U7") (pin "4") (pinfunction "4_4") (pintype "passive"))
    )
    (net (code "2") (name "+5V") (class "Default")
      (node (ref "C1") (pin "2") (pinfunction "2_2") (pintype "passive"))
      (node (ref "C13") (pin "2") (pinfunction "2_2") (pintype "passive"))
      (node (ref "C16") (pin "1") (pinfunction "1_1") (pintype "passive"))
      (node (ref "C17") (pin "1") (pinfunction "1_1") (pintype "passive"))
      (node (ref "C19") (pin "1") (pinfunction "1_1") (pintype "passive"))
      (node (ref "C20") (pin "1") (pinfunction "1_1") (pintype "passive"))
      (node (ref "C21") (pin "1") (pinfunction "1_1") (pintype "passive"))
      (node (ref "C32") (pin "1") (pinfunction "1_1") (pintype "passive"))
      (node (ref "C33") (pin "1") (pinfunction "1_1") (pintype "passive"))
      (node (ref "C34") (pin "1") (pinfunction "1_1") (pintype "passive"))
      (node (ref "C35") (pin "1") (pinfunction "1_1") (pintype "passive"))
      (node (ref "D1") (pin "C") (pinfunction "C_C") (pintype "passive"))
      (node (ref "D2") (pin "C") (pinfunction "C_C") (pintype "passive"))
      (node (ref "D4") (pin "C") (pinfunction "C_C") (pintype "passive"))
      (node (ref "IC1") (pin "8") (pinfunction "VCC_8") (pintype "bidirectional"))
      (node (ref "JP2") (pin "1") (pinfunction "1_1") (pintype "passive"))
      (node (ref "R1") (pin "2") (pinfunction "2_2") (pintype "passive"))
      (node (ref "R10") (pin "2") (pinfunction "2_2") (pintype "passive"))
      (node (ref "R12") (pin "1") (pinfunction "1_1") (pintype "passive"))
      (node (ref "R16") (pin "2") (pinfunction "2_2") (pintype "passive"))
      (node (ref "R17") (pin "2") (pinfunction "2_2") (pintype "passive"))
      (node (ref "R18") (pin "1") (pinfunction "1_1") (pintype "passive"))
      (node (ref "R19") (pin "1") (pinfunction "1_1") (pintype "passive"))
      (node (ref "R2") (pin "2") (pinfunction "2_2") (pintype "passive"))
      (node (ref "R20") (pin "1") (pinfunction "1_1") (pintype "passive"))
      (node (ref "R25") (pin "1") (pinfunction "1_1") (pintype "passive"))
      (node (ref "R26") (pin "1") (pinfunction "1_1") (pintype "passive"))
      (node (ref "R27") (pin "1") (pinfunction "1_1") (pintype "passive"))
      (node (ref "R32") (pin "2") (pinfunction "2_2") (pintype "passive"))
      (node (ref "R33") (pin "2") (pinfunction "2_2") (pintype "passive"))
      (node (ref "R35") (pin "2") (pinfunction "2_2") (pintype "passive"))
      (node (ref "R36") (pin "2") (pinfunction "2_2") (pintype "passive"))
      (node (ref "R4") (pin "2") (pinfunction "2_2") (pintype "passive"))
      (node (ref "R59") (pin "2") (pinfunction "2_2") (pintype "passive"))
      (node (ref "R6") (pin "2") (pinfunction "2_2") (pintype "passive"))
      (node (ref "R61") (pin "2") (pinfunction "2_2") (pintype "passive"))
      (node (ref "R63") (pin "2") (pinfunction "2_2") (pintype "passive"))
      (node (ref "R65") (pin "2") (pinfunction "2_2") (pintype "passive"))
      (node (ref "R7") (pin "2") (pinfunction "2_2") (pintype "passive"))
      (node (ref "R8") (pin "2") (pinfunction "2_2") (pintype "passive"))
      (node (ref "SV10") (pin "1") (pinfunction "1_1") (pintype "passive"))
      (node (ref "SV11") (pin "1") (pinfunction "1_1") (pintype "passive"))
      (node (ref "SV14") (pin "1") (pinfunction "1_1") (pintype "passive"))
      (node (ref "SV15") (pin "1") (pinfunction "1_1") (pintype "passive"))
      (node (ref "SV16") (pin "1") (pinfunction "1_1") (pintype "passive"))
      (node (ref "SV17") (pin "1") (pinfunction "1_1") (pintype "passive"))
      (node (ref "SV2") (pin "1") (pinfunction "1_1") (pintype "passive"))
      (node (ref "SV20") (pin "4") (pinfunction "4_4") (pintype "passive"))
      (node (ref "SV21") (pin "1") (pinfunction "1_1") (pintype "passive"))
      (node (ref "SV3") (pin "1") (pinfunction "1_1") (pintype "passive"))
      (node (ref "SV4") (pin "5") (pinfunction "5_5") (pintype "passive"))
      (node (ref "SV5") (pin "1") (pinfunction "1_1") (pintype "passive"))
      (node (ref "SV6") (pin "6") (pinfunction "6_6") (pintype "passive"))
      (node (ref "SV7") (pin "6") (pinfunction "6_6") (pintype "passive"))
      (node (ref "SV8") (pin "6") (pinfunction "6_6") (pintype "passive"))
      (node (ref "SV9") (pin "6") (pinfunction "6_6") (pintype "passive"))
      (node (ref "U$1") (pin "16") (pinfunction "VCC_16") (pintype "power_in"))
      (node (ref "U5") (pin "1") (pinfunction "ADDR_1") (pintype "bidirectional"))
      (node (ref "U5") (pin "8") (pinfunction "VDD_8") (pintype "bidirectional"))
      (node (ref "U6") (pin "8") (pinfunction "VDD_8") (pintype "bidirectional"))
      (node (ref "U7") (pin "3") (pinfunction "IN_3") (pintype "input"))
      (node (ref "U8") (pin "10") (pinfunction "VCC_10") (pintype "power_in"))
      (node (ref "U8") (pin "100") (pinfunction "AVCC_100") (pintype "power_in"))
      (node (ref "U8") (pin "31") (pinfunction "VCC1_31") (pintype "power_in"))
      (node (ref "U8") (pin "61") (pinfunction "VCC2_61") (pintype "power_in"))
      (node (ref "U8") (pin "80") (pinfunction "VCC3_80") (pintype "power_in"))
      (node (ref "X1") (pin "3") (pinfunction "KL_3") (pintype "passive"))
    )
    (net (code "3") (name "A1_N") (class "Default")
      (node (ref "C23") (pin "1") (pinfunction "1_1") (pintype "passive"))
      (node (ref "SV6") (pin "2") (pinfunction "2_2") (pintype "passive"))
      (node (ref "U5") (pin "5") (pinfunction "AIN1_5") (pintype "bidirectional"))
    )
    (net (code "4") (name "A1_P") (class "Default")
      (node (ref "C22") (pin "1") (pinfunction "1_1") (pintype "passive"))
      (node (ref "SV6") (pin "4") (pinfunction "4_4") (pintype "passive"))
      (node (ref "U5") (pin "4") (pinfunction "AIN0_4") (pintype "bidirectional"))
    )
    (net (code "5") (name "A2_N") (class "Default")
      (node (ref "C25") (pin "1") (pinfunction "1_1") (pintype "passive"))
      (node (ref "SV9") (pin "2") (pinfunction "2_2") (pintype "passive"))
      (node (ref "U5") (pin "7") (pinfunction "AIN3_7") (pintype "bidirectional"))
    )
    (net (code "6") (name "A2_P") (class "Default")
      (node (ref "C24") (pin "1") (pinfunction "1_1") (pintype "passive"))
      (node (ref "SV9") (pin "4") (pinfunction "4_4") (pintype "passive"))
      (node (ref "U5") (pin "6") (pinfunction "AIN2_6") (pintype "bidirectional"))
    )
    (net (code "7") (name "ADC0") (class "Default")
      (node (ref "U8") (pin "97") (pinfunction "(ADC0)PF0_97") (pintype "bidirectional"))
    )
    (net (code "8") (name "ADC1") (class "Default")
      (node (ref "SV14") (pin "2") (pinfunction "2_2") (pintype "passive"))
      (node (ref "U8") (pin "96") (pinfunction "(ADC1)PF1_96") (pintype "bidirectional"))
    )
    (net (code "9") (name "ADC2") (class "Default")
      (node (ref "SV15") (pin "2") (pinfunction "2_2") (pintype "passive"))
      (node (ref "U8") (pin "95") (pinfunction "(ADC2)PF2_95") (pintype "bidirectional"))
    )
    (net (code "10") (name "ADC3") (class "Default")
      (node (ref "SV16") (pin "2") (pinfunction "2_2") (pintype "passive"))
      (node (ref "U8") (pin "94") (pinfunction "(ADC3)PF3_94") (pintype "bidirectional"))
    )
    (net (code "11") (name "ADC4") (class "Default")
      (node (ref "SV17") (pin "2") (pinfunction "2_2") (pintype "passive"))
      (node (ref "U8") (pin "93") (pinfunction "(ADC4/TCK)PF4_93") (pintype "bidirectional"))
    )
    (net (code "12") (name "ADC7") (class "Default")
      (node (ref "U8") (pin "90") (pinfunction "(ADC7/TDI)PF7_90") (pintype "bidirectional"))
      (node (ref "X1") (pin "2") (pinfunction "KL_2") (pintype "passive"))
    )
    (net (code "13") (name "ADC8") (class "Default")
      (node (ref "U8") (pin "89") (pinfunction "PK0(ADC8/PCINT16)_89") (pintype "bidirectional"))
    )
    (net (code "14") (name "ADC9") (class "Default")
      (node (ref "U8") (pin "88") (pinfunction "PK1(ADC9/PCINT17)_88") (pintype "bidirectional"))
    )
    (net (code "15") (name "ADC10") (class "Default")
      (node (ref "U8") (pin "87") (pinfunction "PK2(ADC10/PCINT18)_87") (pintype "bidirectional"))
    )
    (net (code "16") (name "ADC11") (class "Default")
      (node (ref "U8") (pin "86") (pinfunction "PK3(ADC11/PCINT19)_86") (pintype "bidirectional"))
    )
    (net (code "17") (name "ADC12") (class "Default")
      (node (ref "U8") (pin "85") (pinfunction "PK4(ADC12/PCINT20)_85") (pintype "bidirectional"))
    )
    (net (code "18") (name "ADC13") (class "Default")
      (node (ref "U8") (pin "84") (pinfunction "PK5(ADC13/PCINT21)_84") (pintype "bidirectional"))
    )
    (net (code "19") (name "ADC14") (class "Default")
      (node (ref "U8") (pin "83") (pinfunction "PK6(ADC14/PCINT22)_83") (pintype "bidirectional"))
    )
    (net (code "20") (name "ADC15") (class "Default")
      (node (ref "U8") (pin "82") (pinfunction "PK7(ADC15/PCINT23)_82") (pintype "bidirectional"))
    )
    (net (code "21") (name "ANT") (class "Default")
      (node (ref "J1") (pin "1") (pinfunction "1_1") (pintype "bidirectional"))
      (node (ref "U3") (pin "9") (pinfunction "ANT_9") (pintype "bidirectional"))
    )
    (net (code "22") (name "AREF") (class "Default")
      (node (ref "C36") (pin "1") (pinfunction "1_1") (pintype "passive"))
      (node (ref "U8") (pin "98") (pinfunction "AREF_98") (pintype "bidirectional"))
    )
    (net (code "23") (name "B1") (class "Default")
      (node (ref "C2") (pin "1") (pinfunction "1_1") (pintype "passive"))
      (node (ref "R32") (pin "1") (pinfunction "1_1") (pintype "passive"))
      (node (ref "U1") (pin "3") (pinfunction "3_3") (pintype "passive"))
      (node (ref "U1") (pin "4") (pinfunction "4_4") (pintype "passive"))
      (node (ref "U8") (pin "53") (pinfunction "(A8)PC0_53") (pintype "bidirectional"))
    )
    (net (code "24") (name "B1_N") (class "Default")
      (node (ref "C27") (pin "1") (pinfunction "1_1") (pintype "passive"))
      (node (ref "SV7") (pin "2") (pinfunction "2_2") (pintype "passive"))
      (node (ref "U6") (pin "5") (pinfunction "AIN1_5") (pintype "bidirectional"))
    )
    (net (code "25") (name "B1_P") (class "Default")
      (node (ref "C26") (pin "1") (pinfunction "1_1") (pintype "passive"))
      (node (ref "SV7") (pin "4") (pinfunction "4_4") (pintype "passive"))
      (node (ref "U6") (pin "4") (pinfunction "AIN0_4") (pintype "bidirectional"))
    )
    (net (code "26") (name "B2") (class "Default")
      (node (ref "C4") (pin "1") (pinfunction "1_1") (pintype "passive"))
      (node (ref "R33") (pin "1") (pinfunction "1_1") (pintype "passive"))
      (node (ref "U2") (pin "3") (pinfunction "3_3") (pintype "passive"))
      (node (ref "U2") (pin "4") (pinfunction "4_4") (pintype "passive"))
      (node (ref "U8") (pin "54") (pinfunction "(A9)PC1_54") (pintype "bidirectional"))
    )
    (net (code "27") (name "B2_N") (class "Default")
      (node (ref "C29") (pin "1") (pinfunction "1_1") (pintype "passive"))
      (node (ref "SV8") (pin "2") (pinfunction "2_2") (pintype "passive"))
      (node (ref "U6") (pin "7") (pinfunction "AIN3_7") (pintype "bidirectional"))
    )
    (net (code "28") (name "B2_P") (class "Default")
      (node (ref "C28") (pin "1") (pinfunction "1_1") (pintype "passive"))
      (node (ref "SV8") (pin "4") (pinfunction "4_4") (pintype "passive"))
      (node (ref "U6") (pin "6") (pinfunction "AIN2_6") (pintype "bidirectional"))
    )
    (net (code "29") (name "B3") (class "Default")
      (node (ref "U8") (pin "55") (pinfunction "(A10)PC2_55") (pintype "bidirectional"))
    )
    (net (code "30") (name "CLK") (class "Default")
      (node (ref "Q10") (pin "2") (pinfunction "S_2") (pintype "passive"))
      (node (ref "R62") (pin "1") (pinfunction "1_1") (pintype "passive"))
      (node (ref "U3") (pin "4") (pinfunction "SCK_4") (pintype "input"))
    )
    (net (code "31") (name "CS") (class "Default")
      (node (ref "Q11") (pin "2") (pinfunction "S_2") (pintype "passive"))
      (node (ref "R64") (pin "1") (pinfunction "1_1") (pintype "passive"))
      (node (ref "U3") (pin "5") (pinfunction "NSS_5") (pintype "input"))
    )
    (net (code "32") (name "CS_A") (class "Default")
      (node (ref "Q11") (pin "3") (pinfunction "D_3") (pintype "passive"))
      (node (ref "R65") (pin "1") (pinfunction "1_1") (pintype "passive"))
      (node (ref "U8") (pin "19") (pinfunction "(SS/PCINT0)PB0_19") (pintype "bidirectional"))
    )
    (net (code "33") (name "CS_B") (class "Default")
      (node (ref "SV10") (pin "5") (pinfunction "5_5") (pintype "passive"))
      (node (ref "U8") (pin "18") (pinfunction "PH6(OC2B)_18") (pintype "bidirectional"))
    )
    (net (code "34") (name "CS_C") (class "Default")
      (node (ref "SV3") (pin "5") (pinfunction "5_5") (pintype "passive"))
      (node (ref "U8") (pin "17") (pinfunction "PH5(OC4C)_17") (pintype "bidirectional"))
    )
    (net (code "35") (name "DE") (class "Default")
      (node (ref "IC1") (pin "2") (pinfunction "~{RE}_2") (pintype "bidirectional"))
      (node (ref "IC1") (pin "3") (pinfunction "DE_3") (pintype "bidirectional"))
      (node (ref "R6") (pin "1") (pinfunction "1_1") (pintype "passive"))
      (node (ref "U8") (pin "15") (pinfunction "PH3(OC4A)_15") (pintype "bidirectional"))
    )
    (net (code "36") (name "DI") (class "Default")
      (node (ref "Q8") (pin "2") (pinfunction "S_2") (pintype "passive"))
      (node (ref "R58") (pin "1") (pinfunction "1_1") (pintype "passive"))
      (node (ref "U3") (pin "3") (pinfunction "MOSI_3") (pintype "output"))
    )
    (net (code "37") (name "DIO0") (class "Default")
      (node (ref "U3") (pin "14") (pinfunction "DIO0_14") (pintype "bidirectional"))
      (node (ref "U8") (pin "25") (pinfunction "(OC1B/PCINT6)PB6_25") (pintype "bidirectional"))
    )
    (net (code "38") (name "DO") (class "Default")
      (node (ref "Q9") (pin "2") (pinfunction "S_2") (pintype "passive"))
      (node (ref "R60") (pin "1") (pinfunction "1_1") (pintype "passive"))
      (node (ref "U3") (pin "2") (pinfunction "MISO_2") (pintype "input"))
    )
    (net (code "39") (name "DTR") (class "Default")
      (node (ref "C38") (pin "1") (pinfunction "1_1") (pintype "passive"))
      (node (ref "SV1") (pin "4") (pinfunction "4_4") (pintype "passive"))
      (node (ref "U$1") (pin "13") (pinfunction "DTR_13") (pintype "bidirectional"))
    )
    (net (code "40") (name "EN_AM") (class "Default")
      (node (ref "R47") (pin "2") (pinfunction "2_2") (pintype "passive"))
      (node (ref "U8") (pin "92") (pinfunction "(ADC5/TMS)PF5_92") (pintype "bidirectional"))
    )
    (net (code "41") (name "EN_BME") (class "Default")
      (node (ref "R37") (pin "1") (pinfunction "1_1") (pintype "passive"))
      (node (ref "U8") (pin "91") (pinfunction "(ADC6/TDO)PF6_91") (pintype "bidirectional"))
    )
    (net (code "42") (name "EN_OPC") (class "Default")
      (node (ref "R56") (pin "1") (pinfunction "1_1") (pintype "passive"))
      (node (ref "U8") (pin "16") (pinfunction "PH4(OC4B)_16") (pintype "bidirectional"))
    )
    (net (code "43") (name "EN_SENS1") (class "Default")
      (node (ref "R42") (pin "1") (pinfunction "1_1") (pintype "passive"))
      (node (ref "U8") (pin "42") (pinfunction "PL7_42") (pintype "bidirectional"))
    )
    (net (code "44") (name "EN_SENS2") (class "Default")
      (node (ref "R43") (pin "1") (pinfunction "1_1") (pintype "passive"))
      (node (ref "U8") (pin "45") (pinfunction "(RXD1/INT2)PD2_45") (pintype "bidirectional"))
    )
    (net (code "45") (name "EN_SENS3") (class "Default")
      (node (ref "R51") (pin "1") (pinfunction "1_1") (pintype "passive"))
      (node (ref "U8") (pin "46") (pinfunction "(TXD1/INT3)PD3_46") (pintype "bidirectional"))
    )
    (net (code "46") (name "EN_SENS4") (class "Default")
      (node (ref "R54") (pin "1") (pinfunction "1_1") (pintype "passive"))
      (node (ref "U8") (pin "47") (pinfunction "(ICP1)PD4_47") (pintype "bidirectional"))
    )
    (net (code "47") (name "GND") (class "Default")
      (node (ref "C1") (pin "1") (pinfunction "1_1") (pintype "passive"))
      (node (ref "C11") (pin "2") (pinfunction "2_2") (pintype "passive"))
      (node (ref "C13") (pin "1") (pinfunction "1_1") (pintype "passive"))
      (node (ref "C14") (pin "2") (pinfunction "2_2") (pintype "passive"))
      (node (ref "C15") (pin "2") (pinfunction "2_2") (pintype "passive"))
      (node (ref "C16") (pin "2") (pinfunction "2_2") (pintype "passive"))
      (node (ref "C17") (pin "2") (pinfunction "2_2") (pintype "passive"))
      (node (ref "C18") (pin "2") (pinfunction "2_2") (pintype "passive"))
      (node (ref "C19") (pin "2") (pinfunction "2_2") (pintype "passive"))
      (node (ref "C2") (pin "2") (pinfunction "2_2") (pintype "passive"))
      (node (ref "C20") (pin "2") (pinfunction "2_2") (pintype "passive"))
      (node (ref "C21") (pin "2") (pinfunction "2_2") (pintype "passive"))
      (node (ref "C22") (pin "2") (pinfunction "2_2") (pintype "passive"))
      (node (ref "C23") (pin "2") (pinfunction "2_2") (pintype "passive"))
      (node (ref "C24") (pin "2") (pinfunction "2_2") (pintype "passive"))
      (node (ref "C25") (pin "2") (pinfunction "2_2") (pintype "passive"))
      (node (ref "C26") (pin "2") (pinfunction "2_2") (pintype "passive"))
      (node (ref "C27") (pin "2") (pinfunction "2_2") (pintype "passive"))
      (node (ref "C28") (pin "2") (pinfunction "2_2") (pintype "passive"))
      (node (ref "C29") (pin "2") (pinfunction "2_2") (pintype "passive"))
      (node (ref "C30") (pin "1") (pinfunction "1_1") (pintype "passive"))
      (node (ref "C31") (pin "2") (pinfunction "2_2") (pintype "passive"))
      (node (ref "C32") (pin "2") (pinfunction "2_2") (pintype "passive"))
      (node (ref "C33") (pin "2") (pinfunction "2_2") (pintype "passive"))
      (node (ref "C34") (pin "2") (pinfunction "2_2") (pintype "passive"))
      (node (ref "C35") (pin "2") (pinfunction "2_2") (pintype "passive"))
      (node (ref "C36") (pin "2") (pinfunction "2_2") (pintype "passive"))
      (node (ref "C37") (pin "2") (pinfunction "2_2") (pintype "passive"))
      (node (ref "C4") (pin "2") (pinfunction "2_2") (pintype "passive"))
      (node (ref "C8") (pin "1") (pinfunction "1_1") (pintype "passive"))
      (node (ref "C9") (pin "2") (pinfunction "2_2") (pintype "passive"))
      (node (ref "H1") (pin "B3,2") (pinfunction "MOUNT_B3,2") (pintype "passive"))
      (node (ref "H2") (pin "B3,2") (pinfunction "MOUNT_B3,2") (pintype "passive"))
      (node (ref "H3") (pin "B3,2") (pinfunction "MOUNT_B3,2") (pintype "passive"))
      (node (ref "H4") (pin "B3,2") (pinfunction "MOUNT_B3,2") (pintype "passive"))
      (node (ref "IC1") (pin "5") (pinfunction "GND_5") (pintype "bidirectional"))
      (node (ref "J1") (pin "2") (pinfunction "2_2") (pintype "bidirectional"))
      (node (ref "J1") (pin "3") (pinfunction "3_3") (pintype "bidirectional"))
      (node (ref "J1") (pin "4") (pinfunction "4_4") (pintype "bidirectional"))
      (node (ref "J1") (pin "5") (pinfunction "5_5") (pintype "bidirectional"))
      (node (ref "J2") (pin "5") (pinfunction "GND_5") (pintype "passive"))
      (node (ref "J2") (pin "S1") (pinfunction "S_S1") (pintype "passive"))
      (node (ref "J2") (pin "S2") (pinfunction "S_S2") (pintype "passive"))
      (node (ref "J2") (pin "S3") (pinfunction "S_S3") (pintype "passive"))
      (node (ref "J2") (pin "S4") (pinfunction "S_S4") (pintype "passive"))
      (node (ref "LED1") (pin "C") (pinfunction "C_C") (pintype "passive"))
      (node (ref "LED2") (pin "C") (pinfunction "C_C") (pintype "passive"))
      (node (ref "Q1") (pin "2") (pinfunction "S_2") (pintype "passive"))
      (node (ref "Q2") (pin "2") (pinfunction "S_2") (pintype "passive"))
      (node (ref "Q3") (pin "2") (pinfunction "S_2") (pintype "passive"))
      (node (ref "Q4") (pin "2") (pinfunction "S_2") (pintype "passive"))
      (node (ref "Q5") (pin "2") (pinfunction "S_2") (pintype "passive"))
      (node (ref "Q6") (pin "2") (pinfunction "S_2") (pintype "passive"))
      (node (ref "Q7") (pin "2") (pinfunction "S_2") (pintype "passive"))
      (node (ref "R38") (pin "1") (pinfunction "1_1") (pintype "passive"))
      (node (ref "R39") (pin "1") (pinfunction "1_1") (pintype "passive"))
      (node (ref "R40") (pin "1") (pinfunction "1_1") (pintype "passive"))
      (node (ref "R41") (pin "1") (pinfunction "1_1") (pintype "passive"))
      (node (ref "R44") (pin "2") (pinfunction "2_2") (pintype "passive"))
      (node (ref "R45") (pin "1") (pinfunction "1_1") (pintype "passive"))
      (node (ref "R46") (pin "2") (pinfunction "2_2") (pintype "passive"))
      (node (ref "R48") (pin "1") (pinfunction "1_1") (pintype "passive"))
      (node (ref "R49") (pin "1") (pinfunction "1_1") (pintype "passive"))
      (node (ref "R50") (pin "1") (pinfunction "1_1") (pintype "passive"))
      (node (ref "R52") (pin "1") (pinfunction "1_1") (pintype "passive"))
      (node (ref "R53") (pin "1") (pinfunction "1_1") (pintype "passive"))
      (node (ref "R55") (pin "1") (pinfunction "1_1") (pintype "passive"))
      (node (ref "R57") (pin "2") (pinfunction "2_2") (pintype "passive"))
      (node (ref "R9") (pin "2") (pinfunction "2_2") (pintype "passive"))
      (node (ref "SV1") (pin "5") (pinfunction "5_5") (pintype "passive"))
      (node (ref "SV12") (pin "4") (pinfunction "4_4") (pintype "passive"))
      (node (ref "SV13") (pin "4") (pinfunction "4_4") (pintype "passive"))
      (node (ref "SV14") (pin "3") (pinfunction "3_3") (pintype "passive"))
      (node (ref "SV15") (pin "3") (pinfunction "3_3") (pintype "passive"))
      (node (ref "SV16") (pin "3") (pinfunction "3_3") (pintype "passive"))
      (node (ref "SV17") (pin "3") (pinfunction "3_3") (pintype "passive"))
      (node (ref "SV2") (pin "4") (pinfunction "4_4") (pintype "passive"))
      (node (ref "SV20") (pin "1") (pinfunction "1_1") (pintype "passive"))
      (node (ref "SV21") (pin "4") (pinfunction "4_4") (pintype "passive"))
      (node (ref "SV3") (pin "6") (pinfunction "6_6") (pintype "passive"))
      (node (ref "SV4") (pin "1") (pinfunction "1_1") (pintype "passive"))
      (node (ref "U$1") (pin "1") (pinfunction "GND_1") (pintype "power_in"))
      (node (ref "U1") (pin "1") (pinfunction "1_1") (pintype "passive"))
      (node (ref "U1") (pin "2") (pinfunction "2_2") (pintype "passive"))
      (node (ref "U2") (pin "1") (pinfunction "1_1") (pintype "passive"))
      (node (ref "U2") (pin "2") (pinfunction "2_2") (pintype "passive"))
      (node (ref "U3") (pin "1") (pinfunction "GND_1") (pintype "power_in"))
      (node (ref "U3") (pin "10") (pinfunction "GND_10") (pintype "power_in"))
      (node (ref "U3") (pin "8") (pinfunction "GND_8") (pintype "power_in"))
      (node (ref "U5") (pin "3") (pinfunction "VSS_3") (pintype "bidirectional"))
      (node (ref "U6") (pin "1") (pinfunction "ADDR_1") (pintype "bidirectional"))
      (node (ref "U6") (pin "3") (pinfunction "VSS_3") (pintype "bidirectional"))
      (node (ref "U7") (pin "1") (pinfunction "ADJ/GND_1") (pintype "power_in"))
      (node (ref "U8") (pin "11") (pinfunction "GND_11") (pintype "power_in"))
      (node (ref "U8") (pin "32") (pinfunction "GND1_32") (pintype "power_in"))
      (node (ref "U8") (pin "62") (pinfunction "GND2_62") (pintype "power_in"))
      (node (ref "U8") (pin "81") (pinfunction "GND3_81") (pintype "power_in"))
      (node (ref "U8") (pin "99") (pinfunction "AGND_99") (pintype "power_in"))
      (node (ref "U9") (pin "1") (pinfunction "1_1") (pintype "passive"))
      (node (ref "U9") (pin "2") (pinfunction "2_2") (pintype "passive"))
      (node (ref "X1") (pin "1") (pinfunction "KL_1") (pintype "passive"))
      (node (ref "X2") (pin "2") (pinfunction "KL_2") (pintype "passive"))
      (node (ref "X4") (pin "1") (pinfunction "KL_1") (pintype "passive"))
    )
    (net (code "48") (name "L1") (class "Default")
      (node (ref "R11") (pin "2") (pinfunction "2_2") (pintype "passive"))
      (node (ref "U8") (pin "26") (pinfunction "(OC0A/OC1C/PCINT7)PB7_26") (pintype "bidirectional"))
    )
    (net (code "49") (name "MISO") (class "Default")
      (node (ref "Q9") (pin "3") (pinfunction "D_3") (pintype "passive"))
      (node (ref "R61") (pin "1") (pinfunction "1_1") (pintype "passive"))
      (node (ref "SV10") (pin "2") (pinfunction "2_2") (pintype "passive"))
      (node (ref "SV3") (pin "2") (pinfunction "2_2") (pintype "passive"))
      (node (ref "SV4") (pin "6") (pinfunction "6_6") (pintype "passive"))
      (node (ref "TP3") (pin "TP") (pinfunction "TP_TP") (pintype "input"))
      (node (ref "U8") (pin "22") (pinfunction "(MISO/PCINT3)PB3_22") (pintype "bidirectional"))
    )
    (net (code "50") (name "MOSI") (class "Default")
      (node (ref "Q8") (pin "3") (pinfunction "D_3") (pintype "passive"))
      (node (ref "R59") (pin "1") (pinfunction "1_1") (pintype "passive"))
      (node (ref "SV10") (pin "3") (pinfunction "3_3") (pintype "passive"))
      (node (ref "SV3") (pin "3") (pinfunction "3_3") (pintype "passive"))
      (node (ref "SV4") (pin "3") (pinfunction "3_3") (pintype "passive"))
      (node (ref "TP4") (pin "TP") (pinfunction "TP_TP") (pintype "input"))
      (node (ref "U8") (pin "21") (pinfunction "(MOSI/PCINT2)PB2_21") (pintype "bidirectional"))
    )
    (net (code "51") (name "NRST") (class "Default")
      (node (ref "C37") (pin "1") (pinfunction "1_1") (pintype "passive"))
      (node (ref "C38") (pin "2") (pinfunction "2_2") (pintype "passive"))
      (node (ref "R7") (pin "1") (pinfunction "1_1") (pintype "passive"))
      (node (ref "SV4") (pin "2") (pinfunction "2_2") (pintype "passive"))
      (node (ref "TP1") (pin "TP") (pinfunction "TP_TP") (pintype "input"))
      (node (ref "U8") (pin "30") (pinfunction "RESET_30") (pintype "input"))
      (node (ref "U9") (pin "3") (pinfunction "3_3") (pintype "passive"))
      (node (ref "U9") (pin "4") (pinfunction "4_4") (pintype "passive"))
    )
    (net (code "52") (name "Net-(D4-PadA)") (class "Default")
      (node (ref "D4") (pin "A") (pinfunction "A_A") (pintype "passive"))
      (node (ref "SV1") (pin "1") (pinfunction "1_1") (pintype "passive"))
    )
    (net (code "53") (name "Net-(IC1-A)") (class "Default")
      (node (ref "IC1") (pin "6") (pinfunction "A_6") (pintype "bidirectional"))
      (node (ref "R12") (pin "2") (pinfunction "2_2") (pintype "passive"))
      (node (ref "R13") (pin "2") (pinfunction "2_2") (pintype "passive"))
      (node (ref "X2") (pin "1") (pinfunction "KL_1") (pintype "passive"))
    )
    (net (code "54") (name "Net-(IC1-B)") (class "Default")
      (node (ref "IC1") (pin "7") (pinfunction "B_7") (pintype "bidirectional"))
      (node (ref "R13") (pin "1") (pinfunction "1_1") (pintype "passive"))
      (node (ref "R9") (pin "1") (pinfunction "1_1") (pintype "passive"))
      (node (ref "X2") (pin "3") (pinfunction "KL_3") (pintype "passive"))
    )
    (net (code "55") (name "Net-(JP2-Pad2)") (class "Default")
      (node (ref "JP2") (pin "2") (pinfunction "2_2") (pintype "passive"))
      (node (ref "SV12") (pin "1") (pinfunction "1_1") (pintype "passive"))
    )
    (net (code "56") (name "Net-(LED1-PadA)") (class "Default")
      (node (ref "LED1") (pin "A") (pinfunction "A_A") (pintype "passive"))
      (node (ref "R10") (pin "1") (pinfunction "1_1") (pintype "passive"))
    )
    (net (code "57") (name "Net-(LED2-PadA)") (class "Default")
      (node (ref "LED2") (pin "A") (pinfunction "A_A") (pintype "passive"))
      (node (ref "R11") (pin "1") (pinfunction "1_1") (pintype "passive"))
    )
    (net (code "58") (name "Net-(LED3-PadA)") (class "Default")
      (node (ref "LED3") (pin "A") (pinfunction "A_A") (pintype "passive"))
      (node (ref "R17") (pin "1") (pinfunction "1_1") (pintype "passive"))
    )
    (net (code "59") (name "Net-(LED4-PadA)") (class "Default")
      (node (ref "LED4") (pin "A") (pinfunction "A_A") (pintype "passive"))
      (node (ref "R16") (pin "1") (pinfunction "1_1") (pintype "passive"))
    )
    (net (code "60") (name "Net-(Q1-D)") (class "Default")
      (node (ref "Q1") (pin "3") (pinfunction "D_3") (pintype "passive"))
      (node (ref "R39") (pin "2") (pinfunction "2_2") (pintype "passive"))
      (node (ref "SV5") (pin "4") (pinfunction "4_4") (pintype "passive"))
    )
    (net (code "61") (name "Net-(Q1-G)") (class "Default")
      (node (ref "Q1") (pin "1") (pinfunction "G_1") (pintype "passive"))
      (node (ref "R37") (pin "2") (pinfunction "2_2") (pintype "passive"))
      (node (ref "R38") (pin "2") (pinfunction "2_2") (pintype "passive"))
    )
    (net (code "62") (name "Net-(Q2-D)") (class "Default")
      (node (ref "Q2") (pin "3") (pinfunction "D_3") (pintype "passive"))
      (node (ref "R40") (pin "2") (pinfunction "2_2") (pintype "passive"))
      (node (ref "SV6") (pin "1") (pinfunction "1_1") (pintype "passive"))
      (node (ref "SV6") (pin "3") (pinfunction "3_3") (pintype "passive"))
      (node (ref "SV6") (pin "5") (pinfunction "5_5") (pintype "passive"))
    )
    (net (code "63") (name "Net-(Q2-G)") (class "Default")
      (node (ref "Q2") (pin "1") (pinfunction "G_1") (pintype "passive"))
      (node (ref "R41") (pin "2") (pinfunction "2_2") (pintype "passive"))
      (node (ref "R42") (pin "2") (pinfunction "2_2") (pintype "passive"))
    )
    (net (code "64") (name "Net-(Q3-D)") (class "Default")
      (node (ref "Q3") (pin "3") (pinfunction "D_3") (pintype "passive"))
      (node (ref "R45") (pin "2") (pinfunction "2_2") (pintype "passive"))
      (node (ref "SV9") (pin "1") (pinfunction "1_1") (pintype "passive"))
      (node (ref "SV9") (pin "3") (pinfunction "3_3") (pintype "passive"))
      (node (ref "SV9") (pin "5") (pinfunction "5_5") (pintype "passive"))
    )
    (net (code "65") (name "Net-(Q3-G)") (class "Default")
      (node (ref "Q3") (pin "1") (pinfunction "G_1") (pintype "passive"))
      (node (ref "R43") (pin "2") (pinfunction "2_2") (pintype "passive"))
      (node (ref "R44") (pin "1") (pinfunction "1_1") (pintype "passive"))
    )
    (net (code "66") (name "Net-(Q4-D)") (class "Default")
      (node (ref "Q4") (pin "3") (pinfunction "D_3") (pintype "passive"))
      (node (ref "R48") (pin "2") (pinfunction "2_2") (pintype "passive"))
      (node (ref "SV11") (pin "4") (pinfunction "4_4") (pintype "passive"))
    )
    (net (code "67") (name "Net-(Q4-G)") (class "Default")
      (node (ref "Q4") (pin "1") (pinfunction "G_1") (pintype "passive"))
      (node (ref "R46") (pin "1") (pinfunction "1_1") (pintype "passive"))
      (node (ref "R47") (pin "1") (pinfunction "1_1") (pintype "passive"))
    )
    (net (code "68") (name "Net-(Q5-D)") (class "Default")
      (node (ref "Q5") (pin "3") (pinfunction "D_3") (pintype "passive"))
      (node (ref "R49") (pin "2") (pinfunction "2_2") (pintype "passive"))
      (node (ref "SV7") (pin "1") (pinfunction "1_1") (pintype "passive"))
      (node (ref "SV7") (pin "3") (pinfunction "3_3") (pintype "passive"))
      (node (ref "SV7") (pin "5") (pinfunction "5_5") (pintype "passive"))
    )
    (net (code "69") (name "Net-(Q5-G)") (class "Default")
      (node (ref "Q5") (pin "1") (pinfunction "G_1") (pintype "passive"))
      (node (ref "R50") (pin "2") (pinfunction "2_2") (pintype "passive"))
      (node (ref "R51") (pin "2") (pinfunction "2_2") (pintype "passive"))
    )
    (net (code "70") (name "Net-(Q6-D)") (class "Default")
      (node (ref "Q6") (pin "3") (pinfunction "D_3") (pintype "passive"))
      (node (ref "R52") (pin "2") (pinfunction "2_2") (pintype "passive"))
      (node (ref "SV8") (pin "1") (pinfunction "1_1") (pintype "passive"))
      (node (ref "SV8") (pin "3") (pinfunction "3_3") (pintype "passive"))
      (node (ref "SV8") (pin "5") (pinfunction "5_5") (pintype "passive"))
    )
    (net (code "71") (name "Net-(Q6-G)") (class "Default")
      (node (ref "Q6") (pin "1") (pinfunction "G_1") (pintype "passive"))
      (node (ref "R53") (pin "2") (pinfunction "2_2") (pintype "passive"))
      (node (ref "R54") (pin "2") (pinfunction "2_2") (pintype "passive"))
    )
    (net (code "72") (name "Net-(Q7-D)") (class "Default")
      (node (ref "Q7") (pin "3") (pinfunction "D_3") (pintype "passive"))
      (node (ref "R55") (pin "2") (pinfunction "2_2") (pintype "passive"))
      (node (ref "SV10") (pin "6") (pinfunction "6_6") (pintype "passive"))
    )
    (net (code "73") (name "Net-(Q7-G)") (class "Default")
      (node (ref "Q7") (pin "1") (pinfunction "G_1") (pintype "passive"))
      (node (ref "R56") (pin "2") (pinfunction "2_2") (pintype "passive"))
      (node (ref "R57") (pin "1") (pinfunction "1_1") (pintype "passive"))
    )
    (net (code "74") (name "Net-(U$1-RX)") (class "Default")
      (node (ref "R14") (pin "1") (pinfunction "1_1") (pintype "passive"))
      (node (ref "U$1") (pin "3") (pinfunction "RX_3") (pintype "input"))
    )
    (net (code "75") (name "Net-(U$1-TX)") (class "Default")
      (node (ref "R15") (pin "1") (pinfunction "1_1") (pintype "passive"))
      (node (ref "U$1") (pin "2") (pinfunction "TX_2") (pintype "output"))
    )
    (net (code "76") (name "Net-(U$1-XI)") (class "Default")
      (node (ref "C14") (pin "1") (pinfunction "1_1") (pintype "passive"))
      (node (ref "U$1") (pin "7") (pinfunction "XI_7") (pintype "input"))
      (node (ref "Y2") (pin "2") (pinfunction "2_2") (pintype "passive"))
    )
    (net (code "77") (name "Net-(U$1-XO)") (class "Default")
      (node (ref "C15") (pin "1") (pinfunction "1_1") (pintype "passive"))
      (node (ref "U$1") (pin "8") (pinfunction "XO_8") (pintype "output"))
      (node (ref "Y2") (pin "1") (pinfunction "1_1") (pintype "passive"))
    )
    (net (code "78") (name "Net-(U5-ALERT{slash}RDY)") (class "Default")
      (node (ref "R20") (pin "2") (pinfunction "2_2") (pintype "passive"))
      (node (ref "U5") (pin "2") (pinfunction "ALERT/RDY_2") (pintype "bidirectional"))
    )
    (net (code "79") (name "Net-(U6-ALERT{slash}RDY)") (class "Default")
      (node (ref "R27") (pin "2") (pinfunction "2_2") (pintype "passive"))
      (node (ref "U6") (pin "2") (pinfunction "ALERT/RDY_2") (pintype "bidirectional"))
    )
    (net (code "80") (name "Net-(U8-XTAL1)") (class "Default")
      (node (ref "C31") (pin "1") (pinfunction "1_1") (pintype "passive"))
      (node (ref "U8") (pin "34") (pinfunction "XTAL1_34") (pintype "input"))
      (node (ref "Y3") (pin "1") (pinfunction "1_1") (pintype "passive"))
    )
    (net (code "81") (name "Net-(U8-XTAL2)") (class "Default")
      (node (ref "C30") (pin "2") (pinfunction "2_2") (pintype "passive"))
      (node (ref "U8") (pin "33") (pinfunction "XTAL2_33") (pintype "output"))
      (node (ref "Y3") (pin "2") (pinfunction "2_2") (pintype "passive"))
    )
    (net (code "82") (name "Net-(X4B-KL)") (class "Default")
      (node (ref "D2") (pin "A") (pinfunction "A_A") (pintype "passive"))
      (node (ref "X4") (pin "2") (pinfunction "KL_2") (pintype "passive"))
    )
    (net (code "83") (name "RST") (class "Default")
      (node (ref "U3") (pin "6") (pinfunction "RESET_6") (pintype "bidirectional"))
      (node (ref "U8") (pin "24") (pinfunction "(OC1A/PCINT5)PB5_24") (pintype "bidirectional"))
    )
    (net (code "84") (name "RX0") (class "Default")
      (node (ref "LED3") (pin "C") (pinfunction "C_C") (pintype "passive"))
      (node (ref "R15") (pin "2") (pinfunction "2_2") (pintype "passive"))
      (node (ref "SV1") (pin "3") (pinfunction "3_3") (pintype "passive"))
      (node (ref "U8") (pin "2") (pinfunction "(RXD0/PCIN8)PE0_2") (pintype "bidirectional"))
    )
    (net (code "85") (name "RXB") (class "Default")
      (node (ref "SV12") (pin "3") (pinfunction "3_3") (pintype "passive"))
      (node (ref "U8") (pin "63") (pinfunction "PJ0(RXD3/PCINT9)_63") (pintype "bidirectional"))
    )
    (net (code "86") (name "RXR") (class "Default")
      (node (ref "IC1") (pin "1") (pinfunction "RO_1") (pintype "bidirectional"))
      (node (ref "R1") (pin "1") (pinfunction "1_1") (pintype "passive"))
      (node (ref "U8") (pin "12") (pinfunction "PH0(RXD2)_12") (pintype "bidirectional"))
    )
    (net (code "87") (name "SCK") (class "Default")
      (node (ref "Q10") (pin "3") (pinfunction "D_3") (pintype "passive"))
      (node (ref "R63") (pin "1") (pinfunction "1_1") (pintype "passive"))
      (node (ref "SV10") (pin "4") (pinfunction "4_4") (pintype "passive"))
      (node (ref "SV3") (pin "4") (pinfunction "4_4") (pintype "passive"))
      (node (ref "SV4") (pin "4") (pinfunction "4_4") (pintype "passive"))
      (node (ref "TP5") (pin "TP") (pinfunction "TP_TP") (pintype "input"))
      (node (ref "U8") (pin "20") (pinfunction "(SCK/PCINT1)PB1_20") (pintype "bidirectional"))
    )
    (net (code "88") (name "SCL") (class "Default")
      (node (ref "Q13") (pin "3") (pinfunction "D_3") (pintype "passive"))
      (node (ref "R19") (pin "2") (pinfunction "2_2") (pintype "passive"))
      (node (ref "R26") (pin "2") (pinfunction "2_2") (pintype "passive"))
      (node (ref "R36") (pin "1") (pinfunction "1_1") (pintype "passive"))
      (node (ref "R4") (pin "1") (pinfunction "1_1") (pintype "passive"))
      (node (ref "SV11") (pin "3") (pinfunction "3_3") (pintype "passive"))
      (node (ref "SV2") (pin "3") (pinfunction "3_3") (pintype "passive"))
      (node (ref "SV20") (pin "2") (pinfunction "2_2") (pintype "passive"))
      (node (ref "SV21") (pin "3") (pinfunction "3_3") (pintype "passive"))
      (node (ref "SV5") (pin "3") (pinfunction "3_3") (pintype "passive"))
      (node (ref "U5") (pin "10") (pinfunction "SCL_10") (pintype "bidirectional"))
      (node (ref "U6") (pin "10") (pinfunction "SCL_10") (pintype "bidirectional"))
      (node (ref "U8") (pin "43") (pinfunction "(SCL/INT0)PD0_43") (pintype "bidirectional"))
    )
    (net (code "89") (name "SCL3") (class "Default")
      (node (ref "Q13") (pin "2") (pinfunction "S_2") (pintype "passive"))
      (node (ref "R5") (pin "1") (pinfunction "1_1") (pintype "passive"))
      (node (ref "SV13") (pin "3") (pinfunction "3_3") (pintype "passive"))
    )
    (net (code "90") (name "SDA") (class "Default")
      (node (ref "Q12") (pin "3") (pinfunction "D_3") (pintype "passive"))
      (node (ref "R18") (pin "2") (pinfunction "2_2") (pintype "passive"))
      (node (ref "R2") (pin "1") (pinfunction "1_1") (pintype "passive"))
      (node (ref "R25") (pin "2") (pinfunction "2_2") (pintype "passive"))
      (node (ref "R35") (pin "1") (pinfunction "1_1") (pintype "passive"))
      (node (ref "SV11") (pin "2") (pinfunction "2_2") (pintype "passive"))
      (node (ref "SV2") (pin "2") (pinfunction "2_2") (pintype "passive"))
      (node (ref "SV20") (pin "3") (pinfunction "3_3") (pintype "passive"))
      (node (ref "SV21") (pin "2") (pinfunction "2_2") (pintype "passive"))
      (node (ref "SV5") (pin "2") (pinfunction "2_2") (pintype "passive"))
      (node (ref "U5") (pin "9") (pinfunction "SDA_9") (pintype "bidirectional"))
      (node (ref "U6") (pin "9") (pinfunction "SDA_9") (pintype "bidirectional"))
      (node (ref "U8") (pin "44") (pinfunction "(SDA/INT1)PD1_44") (pintype "bidirectional"))
    )
    (net (code "91") (name "SDA3") (class "Default")
      (node (ref "Q12") (pin "2") (pinfunction "S_2") (pintype "passive"))
      (node (ref "R3") (pin "1") (pinfunction "1_1") (pintype "passive"))
      (node (ref "SV13") (pin "2") (pinfunction "2_2") (pintype "passive"))
    )
    (net (code "92") (name "SPEED") (class "Default")
      (node (ref "U8") (pin "1") (pinfunction "(OC0B)PG5_1") (pintype "bidirectional"))
      (node (ref "X1") (pin "4") (pinfunction "KL_4") (pintype "passive"))
    )
    (net (code "93") (name "TX0") (class "Default")
      (node (ref "LED4") (pin "C") (pinfunction "C_C") (pintype "passive"))
      (node (ref "R14") (pin "2") (pinfunction "2_2") (pintype "passive"))
      (node (ref "SV1") (pin "2") (pinfunction "2_2") (pintype "passive"))
      (node (ref "U8") (pin "3") (pinfunction "(TXD0)PE1_3") (pintype "bidirectional"))
    )
    (net (code "94") (name "TXB") (class "Default")
      (node (ref "SV12") (pin "2") (pinfunction "2_2") (pintype "passive"))
      (node (ref "U8") (pin "64") (pinfunction "PJ1(TXD3/PCINT10)_64") (pintype "bidirectional"))
    )
    (net (code "95") (name "TXR") (class "Default")
      (node (ref "IC1") (pin "4") (pinfunction "DI_4") (pintype "bidirectional"))
      (node (ref "R8") (pin "1") (pinfunction "1_1") (pintype "passive"))
      (node (ref "U8") (pin "13") (pinfunction "PH1(TXD2)_13") (pintype "bidirectional"))
    )
    (net (code "96") (name "UD+") (class "Default")
      (node (ref "J2") (pin "3") (pinfunction "D+_3") (pintype "passive"))
      (node (ref "U$1") (pin "5") (pinfunction "UD+_5") (pintype "bidirectional"))
    )
    (net (code "97") (name "UD-") (class "Default")
      (node (ref "J2") (pin "2") (pinfunction "D-_2") (pintype "passive"))
      (node (ref "U$1") (pin "6") (pinfunction "UD-_6") (pintype "bidirectional"))
    )
    (net (code "98") (name "VBUS") (class "Default")
      (node (ref "D1") (pin "A") (pinfunction "A_A") (pintype "passive"))
      (node (ref "J2") (pin "1") (pinfunction "VBUS_1") (pintype "passive"))
    )
    (net (code "99") (name "unconnected-(J2-ID-Pad4)") (class "Default")
      (node (ref "J2") (pin "4") (pinfunction "ID_4") (pintype "passive"))
    )
    (net (code "100") (name "unconnected-(U$1-CTS-Pad9)") (class "Default")
      (node (ref "U$1") (pin "9") (pinfunction "CTS_9") (pintype "bidirectional"))
    )
    (net (code "101") (name "unconnected-(U$1-DCD-Pad12)") (class "Default")
      (node (ref "U$1") (pin "12") (pinfunction "DCD_12") (pintype "bidirectional"))
    )
    (net (code "102") (name "unconnected-(U$1-DSR-Pad10)") (class "Default")
      (node (ref "U$1") (pin "10") (pinfunction "DSR_10") (pintype "bidirectional"))
    )
    (net (code "103") (name "unconnected-(U$1-R232-Pad15)") (class "Default")
      (node (ref "U$1") (pin "15") (pinfunction "R232_15") (pintype "bidirectional"))
    )
    (net (code "104") (name "unconnected-(U$1-RI-Pad11)") (class "Default")
      (node (ref "U$1") (pin "11") (pinfunction "RI_11") (pintype "bidirectional"))
    )
    (net (code "105") (name "unconnected-(U$1-RTS-Pad14)") (class "Default")
      (node (ref "U$1") (pin "14") (pinfunction "RTS_14") (pintype "bidirectional"))
    )
    (net (code "106") (name "unconnected-(U3-DIO1-Pad15)") (class "Default")
      (node (ref "U3") (pin "15") (pinfunction "DIO1_15") (pintype "bidirectional"))
    )
    (net (code "107") (name "unconnected-(U3-DIO2-Pad16)") (class "Default")
      (node (ref "U3") (pin "16") (pinfunction "DIO2_16") (pintype "bidirectional"))
    )
    (net (code "108") (name "unconnected-(U3-DIO3-Pad11)") (class "Default")
      (node (ref "U3") (pin "11") (pinfunction "DIO3_11") (pintype "bidirectional"))
    )
    (net (code "109") (name "unconnected-(U3-DIO4-Pad12)") (class "Default")
      (node (ref "U3") (pin "12") (pinfunction "DIO4_12") (pintype "bidirectional"))
    )
    (net (code "110") (name "unconnected-(U3-DIO5-Pad7)") (class "Default")
      (node (ref "U3") (pin "7") (pinfunction "DIO5_7") (pintype "bidirectional"))
    )
    (net (code "111") (name "unconnected-(U8-(A11)PC3-Pad56)") (class "Default")
      (node (ref "U8") (pin "56") (pinfunction "(A11)PC3_56") (pintype "bidirectional"))
    )
    (net (code "112") (name "unconnected-(U8-(A12)PC4-Pad57)") (class "Default")
      (node (ref "U8") (pin "57") (pinfunction "(A12)PC4_57") (pintype "bidirectional"))
    )
    (net (code "113") (name "unconnected-(U8-(A13)PC5-Pad58)") (class "Default")
      (node (ref "U8") (pin "58") (pinfunction "(A13)PC5_58") (pintype "bidirectional"))
    )
    (net (code "114") (name "unconnected-(U8-(A14)PC6-Pad59)") (class "Default")
      (node (ref "U8") (pin "59") (pinfunction "(A14)PC6_59") (pintype "bidirectional"))
    )
    (net (code "115") (name "unconnected-(U8-(A15)PC7-Pad60)") (class "Default")
      (node (ref "U8") (pin "60") (pinfunction "(A15)PC7_60") (pintype "bidirectional"))
    )
    (net (code "116") (name "unconnected-(U8-(AD0)PA0-Pad78)") (class "Default")
      (node (ref "U8") (pin "78") (pinfunction "(AD0)PA0_78") (pintype "bidirectional"))
    )
    (net (code "117") (name "unconnected-(U8-(AD1)PA1-Pad77)") (class "Default")
      (node (ref "U8") (pin "77") (pinfunction "(AD1)PA1_77") (pintype "bidirectional"))
    )
    (net (code "118") (name "unconnected-(U8-(AD2)PA2-Pad76)") (class "Default")
      (node (ref "U8") (pin "76") (pinfunction "(AD2)PA2_76") (pintype "bidirectional"))
    )
    (net (code "119") (name "unconnected-(U8-(AD3)PA3-Pad75)") (class "Default")
      (node (ref "U8") (pin "75") (pinfunction "(AD3)PA3_75") (pintype "bidirectional"))
    )
    (net (code "120") (name "unconnected-(U8-(AD4)PA4-Pad74)") (class "Default")
      (node (ref "U8") (pin "74") (pinfunction "(AD4)PA4_74") (pintype "bidirectional"))
    )
    (net (code "121") (name "unconnected-(U8-(AD5)PA5-Pad73)") (class "Default")
      (node (ref "U8") (pin "73") (pinfunction "(AD5)PA5_73") (pintype "bidirectional"))
    )
    (net (code "122") (name "unconnected-(U8-(AD6)PA6-Pad72)") (class "Default")
      (node (ref "U8") (pin "72") (pinfunction "(AD6)PA6_72") (pintype "bidirectional"))
    )
    (net (code "123") (name "unconnected-(U8-(AD7)PA7-Pad71)") (class "Default")
      (node (ref "U8") (pin "71") (pinfunction "(AD7)PA7_71") (pintype "bidirectional"))
    )
    (net (code "124") (name "unconnected-(U8-(ALE)PG2-Pad70)") (class "Default")
      (node (ref "U8") (pin "70") (pinfunction "(ALE)PG2_70") (pintype "bidirectional"))
    )
    (net (code "125") (name "unconnected-(U8-(CLKO{slash}ICP3{slash}INT7)PE7-Pad9)") (class "Default")
      (node (ref "U8") (pin "9") (pinfunction "(CLKO/ICP3/INT7)PE7_9") (pintype "bidirectional"))
    )
    (net (code "126") (name "unconnected-(U8-(OC2A{slash}PCINT4)PB4-Pad23)") (class "Default")
      (node (ref "U8") (pin "23") (pinfunction "(OC2A/PCINT4)PB4_23") (pintype "bidirectional"))
    )
    (net (code "127") (name "unconnected-(U8-(OC3A{slash}AIN1)PE3-Pad5)") (class "Default")
      (node (ref "U8") (pin "5") (pinfunction "(OC3A/AIN1)PE3_5") (pintype "bidirectional"))
    )
    (net (code "128") (name "unconnected-(U8-(OC3B{slash}INT4)PE4-Pad6)") (class "Default")
      (node (ref "U8") (pin "6") (pinfunction "(OC3B/INT4)PE4_6") (pintype "bidirectional"))
    )
    (net (code "129") (name "unconnected-(U8-(OC3C{slash}INT5)PE5-Pad7)") (class "Default")
      (node (ref "U8") (pin "7") (pinfunction "(OC3C/INT5)PE5_7") (pintype "bidirectional"))
    )
    (net (code "130") (name "unconnected-(U8-(RD)PG1-Pad52)") (class "Default")
      (node (ref "U8") (pin "52") (pinfunction "(RD)PG1_52") (pintype "bidirectional"))
    )
    (net (code "131") (name "unconnected-(U8-(T0)PD7-Pad50)") (class "Default")
      (node (ref "U8") (pin "50") (pinfunction "(T0)PD7_50") (pintype "bidirectional"))
    )
    (net (code "132") (name "unconnected-(U8-(T1)PD6-Pad49)") (class "Default")
      (node (ref "U8") (pin "49") (pinfunction "(T1)PD6_49") (pintype "bidirectional"))
    )
    (net (code "133") (name "unconnected-(U8-(T3{slash}INT6)PE6-Pad8)") (class "Default")
      (node (ref "U8") (pin "8") (pinfunction "(T3/INT6)PE6_8") (pintype "bidirectional"))
    )
    (net (code "134") (name "unconnected-(U8-(TOSC1)PG4-Pad29)") (class "Default")
      (node (ref "U8") (pin "29") (pinfunction "(TOSC1)PG4_29") (pintype "bidirectional"))
    )
    (net (code "135") (name "unconnected-(U8-(TOSC2)PG3-Pad28)") (class "Default")
      (node (ref "U8") (pin "28") (pinfunction "(TOSC2)PG3_28") (pintype "bidirectional"))
    )
    (net (code "136") (name "unconnected-(U8-(WR)PG0-Pad51)") (class "Default")
      (node (ref "U8") (pin "51") (pinfunction "(WR)PG0_51") (pintype "bidirectional"))
    )
    (net (code "137") (name "unconnected-(U8-(XCK0{slash}AIN0)PE2-Pad4)") (class "Default")
      (node (ref "U8") (pin "4") (pinfunction "(XCK0/AIN0)PE2_4") (pintype "bidirectional"))
    )
    (net (code "138") (name "unconnected-(U8-(XCK1)PD5-Pad48)") (class "Default")
      (node (ref "U8") (pin "48") (pinfunction "(XCK1)PD5_48") (pintype "bidirectional"))
    )
    (net (code "139") (name "unconnected-(U8-PH2(XCK2)-Pad14)") (class "Default")
      (node (ref "U8") (pin "14") (pinfunction "PH2(XCK2)_14") (pintype "bidirectional"))
    )
    (net (code "140") (name "unconnected-(U8-PH7(T4)-Pad27)") (class "Default")
      (node (ref "U8") (pin "27") (pinfunction "PH7(T4)_27") (pintype "bidirectional"))
    )
    (net (code "141") (name "unconnected-(U8-PJ2(XCK3{slash}PCINT11)-Pad65)") (class "Default")
      (node (ref "U8") (pin "65") (pinfunction "PJ2(XCK3/PCINT11)_65") (pintype "bidirectional"))
    )
    (net (code "142") (name "unconnected-(U8-PJ3(PCINT12)-Pad66)") (class "Default")
      (node (ref "U8") (pin "66") (pinfunction "PJ3(PCINT12)_66") (pintype "bidirectional"))
    )
    (net (code "143") (name "unconnected-(U8-PJ4(PCINT13)-Pad67)") (class "Default")
      (node (ref "U8") (pin "67") (pinfunction "PJ4(PCINT13)_67") (pintype "bidirectional"))
    )
    (net (code "144") (name "unconnected-(U8-PJ5(PCINT14)-Pad68)") (class "Default")
      (node (ref "U8") (pin "68") (pinfunction "PJ5(PCINT14)_68") (pintype "bidirectional"))
    )
    (net (code "145") (name "unconnected-(U8-PJ6(PCINT15)-Pad69)") (class "Default")
      (node (ref "U8") (pin "69") (pinfunction "PJ6(PCINT15)_69") (pintype "bidirectional"))
    )
    (net (code "146") (name "unconnected-(U8-PJ7-Pad79)") (class "Default")
      (node (ref "U8") (pin "79") (pinfunction "PJ7_79") (pintype "bidirectional"))
    )
    (net (code "147") (name "unconnected-(U8-PL0(ICP4)-Pad35)") (class "Default")
      (node (ref "U8") (pin "35") (pinfunction "PL0(ICP4)_35") (pintype "bidirectional"))
    )
    (net (code "148") (name "unconnected-(U8-PL1(ICP5)-Pad36)") (class "Default")
      (node (ref "U8") (pin "36") (pinfunction "PL1(ICP5)_36") (pintype "bidirectional"))
    )
    (net (code "149") (name "unconnected-(U8-PL2(T5)-Pad37)") (class "Default")
      (node (ref "U8") (pin "37") (pinfunction "PL2(T5)_37") (pintype "bidirectional"))
    )
    (net (code "150") (name "unconnected-(U8-PL3(OC5A)-Pad38)") (class "Default")
      (node (ref "U8") (pin "38") (pinfunction "PL3(OC5A)_38") (pintype "bidirectional"))
    )
    (net (code "151") (name "unconnected-(U8-PL4(OC5B)-Pad39)") (class "Default")
      (node (ref "U8") (pin "39") (pinfunction "PL4(OC5B)_39") (pintype "bidirectional"))
    )
    (net (code "152") (name "unconnected-(U8-PL5(OC5C)-Pad40)") (class "Default")
      (node (ref "U8") (pin "40") (pinfunction "PL5(OC5C)_40") (pintype "bidirectional"))
    )
    (net (code "153") (name "unconnected-(U8-PL6-Pad41)") (class "Default")
      (node (ref "U8") (pin "41") (pinfunction "PL6_41") (pintype "bidirectional"))
    )
  )
)
